# display.net
KiCad netlist of a schematic drawn in EAGLE
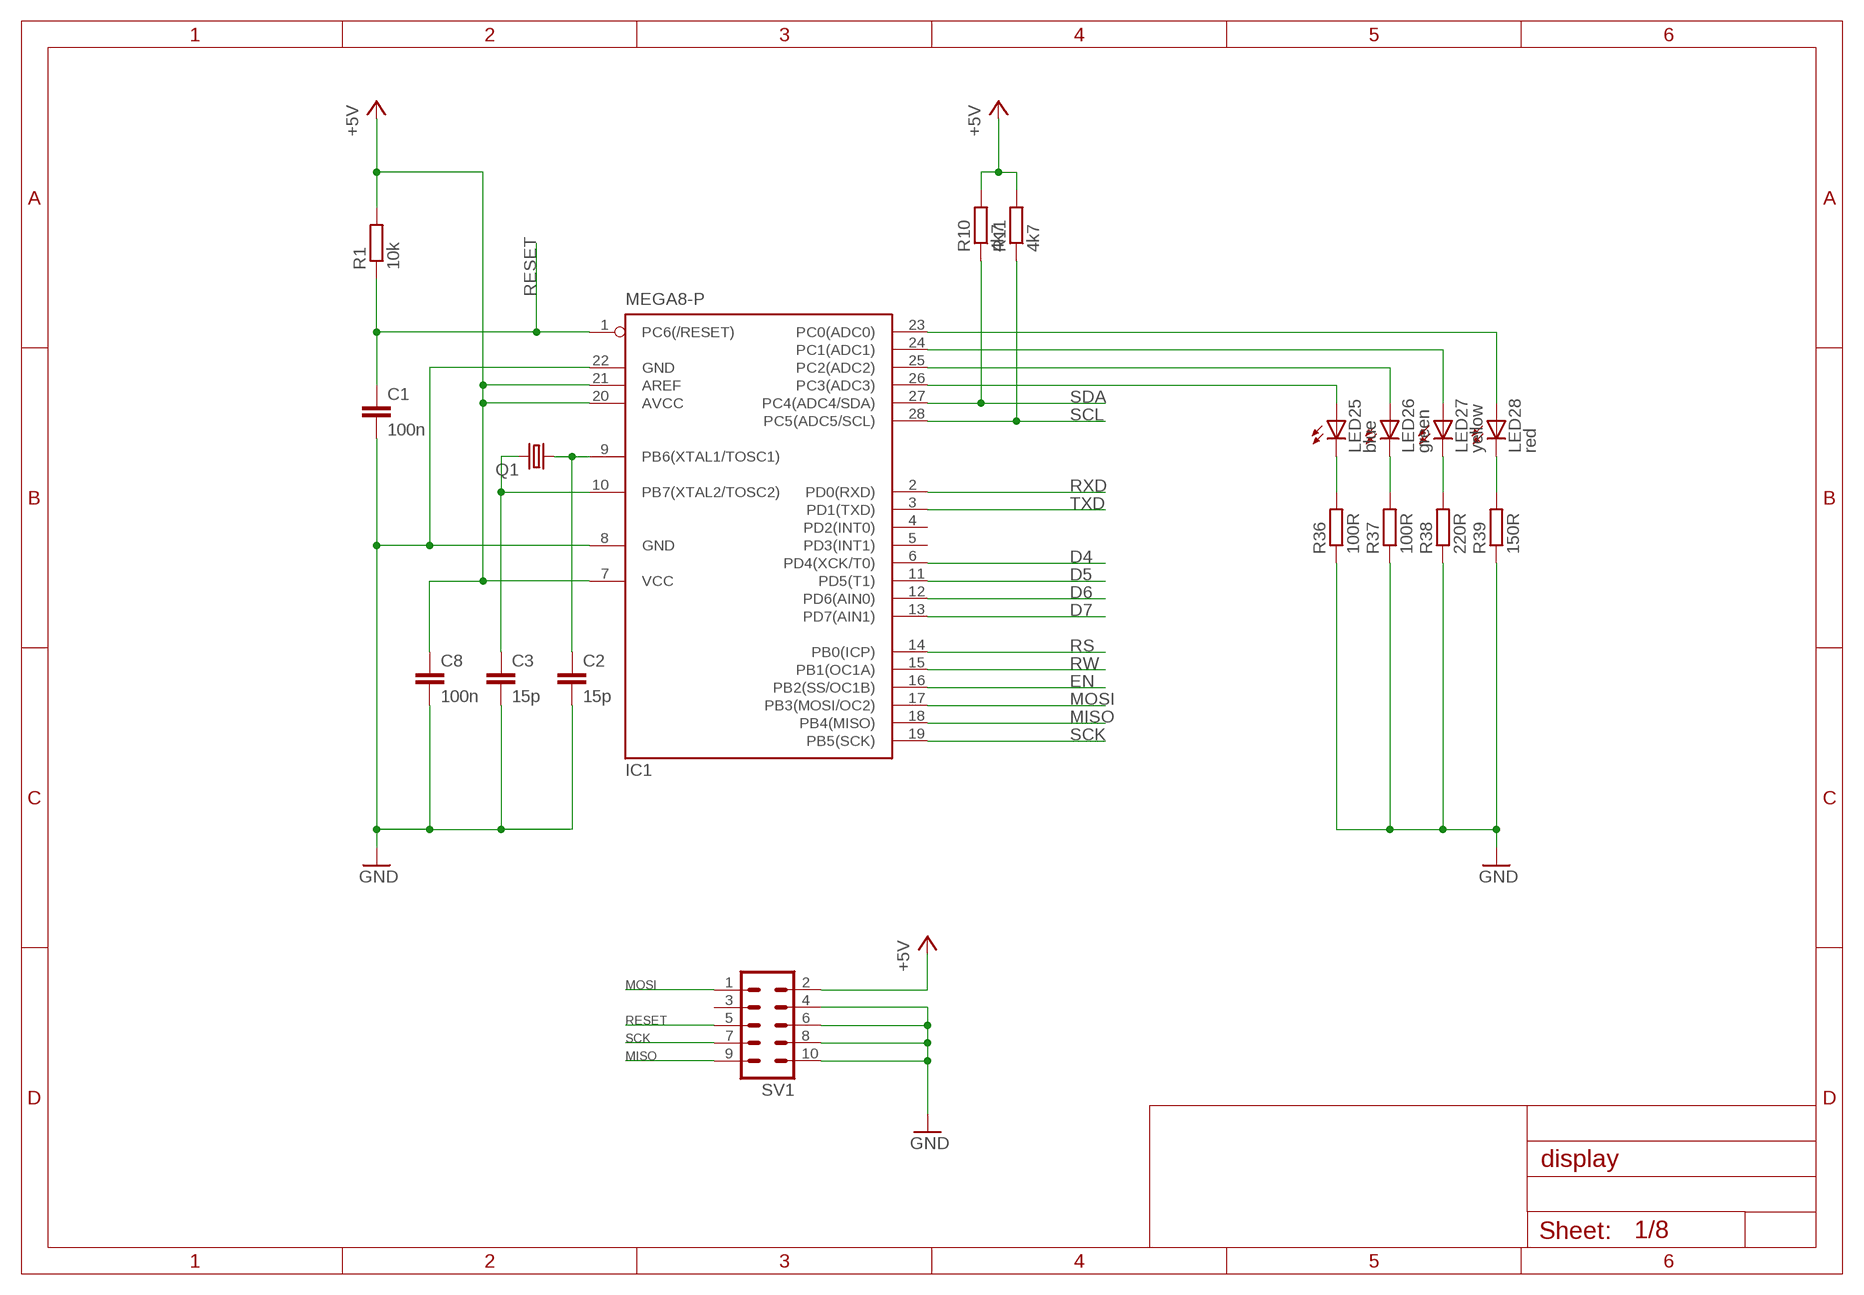
[diagram p0: schematic, sheet 1]
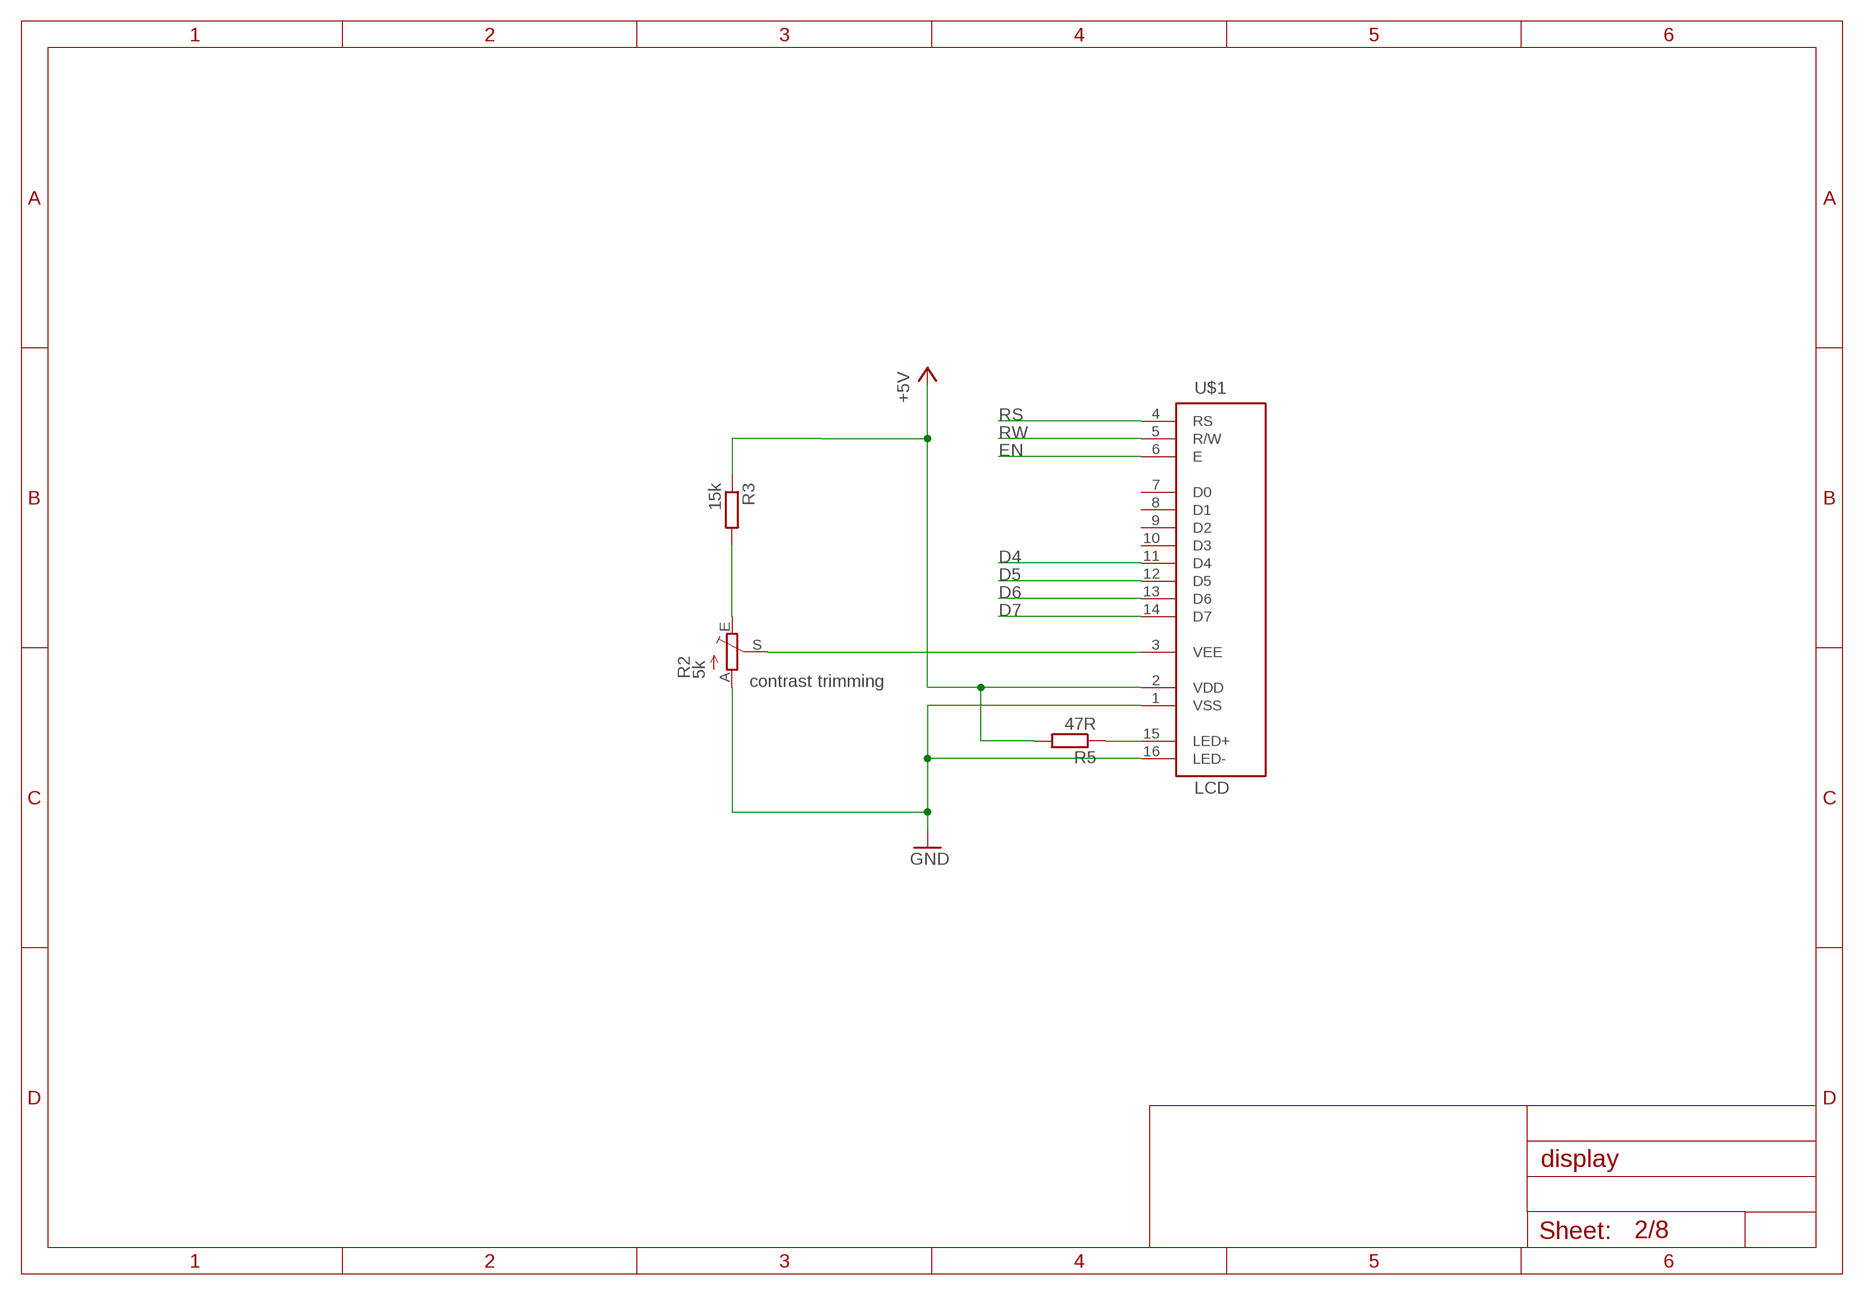
[diagram p1: schematic, sheet 2]
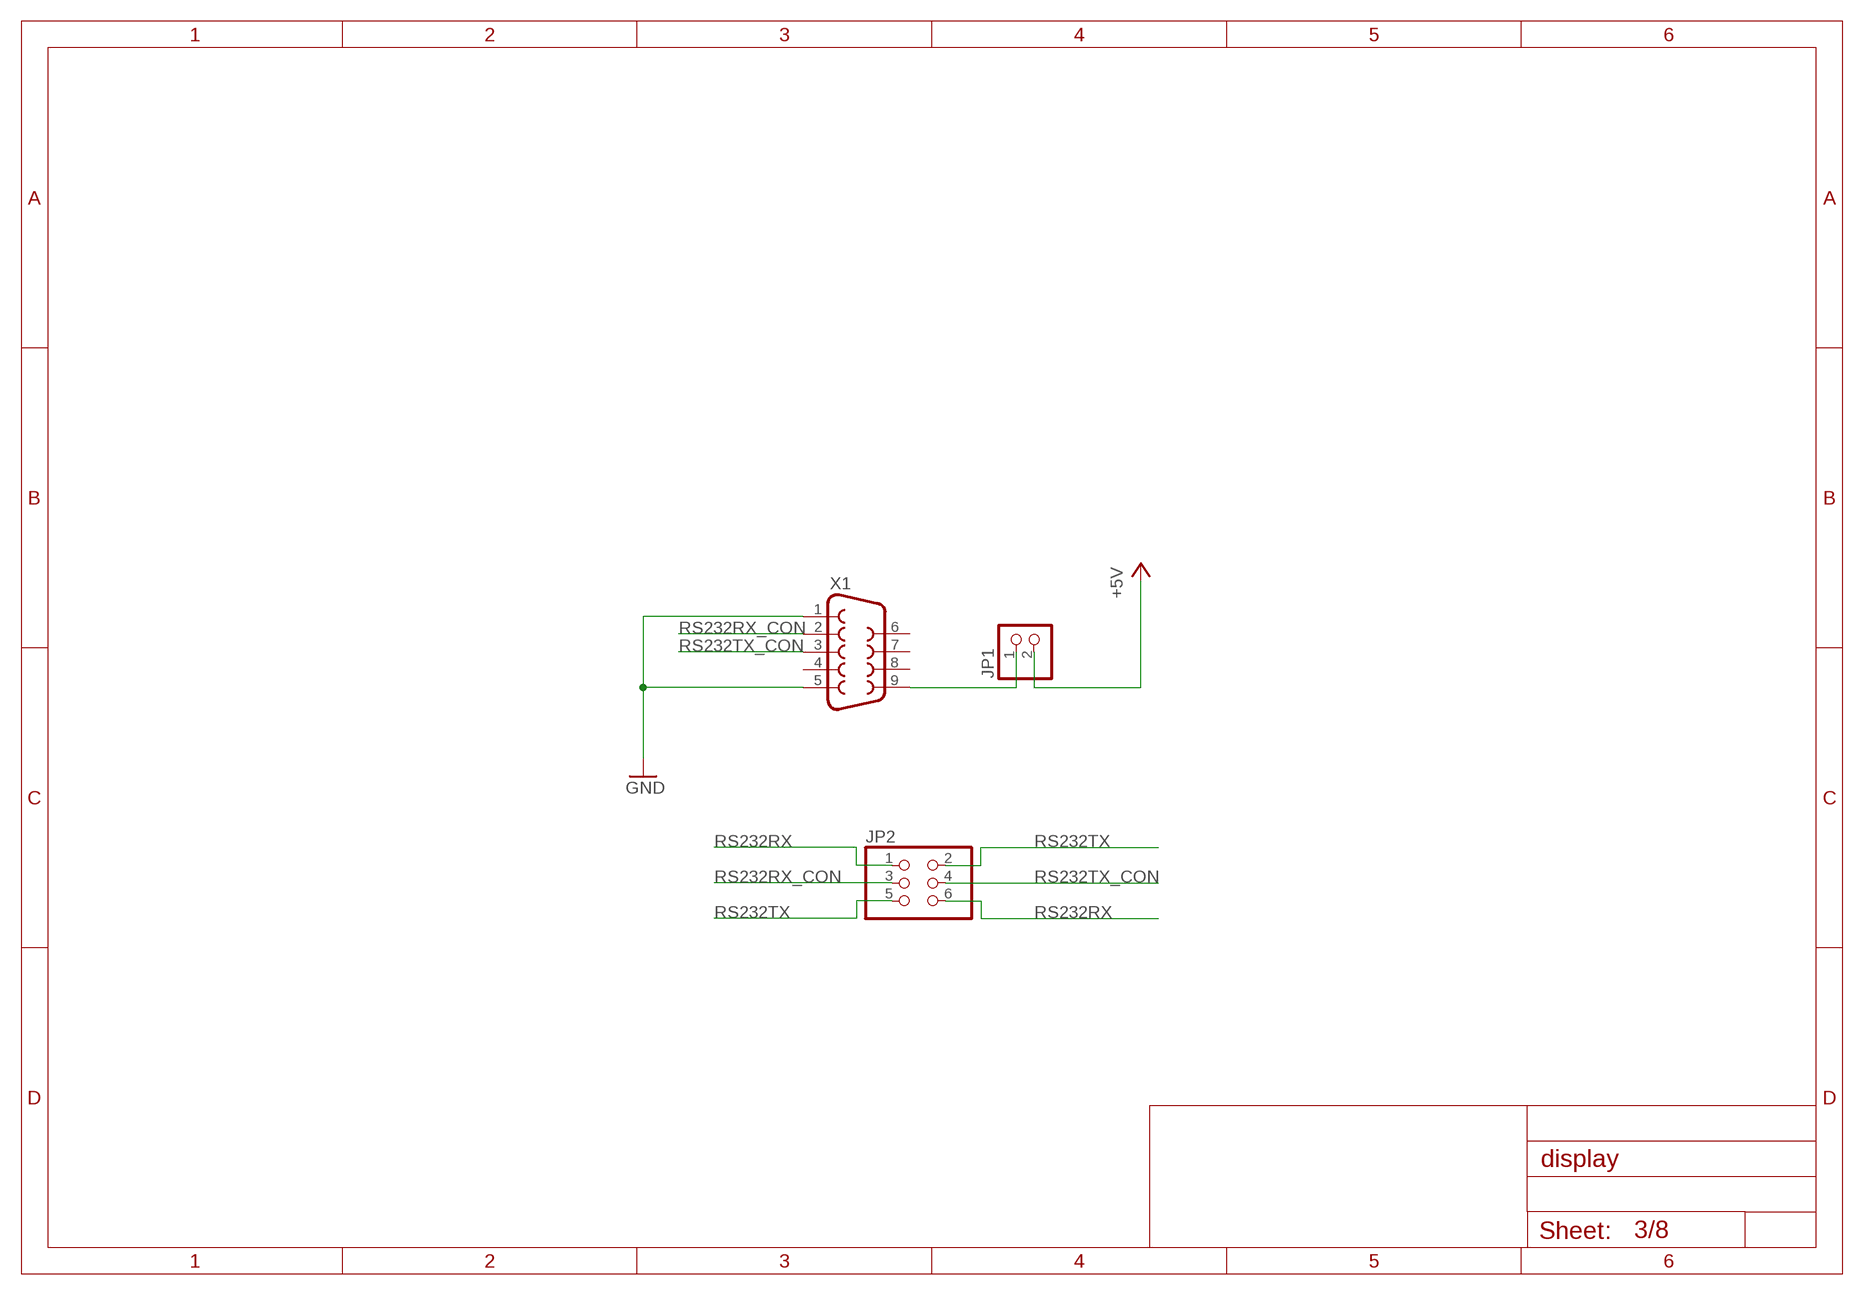
[diagram p2: schematic, sheet 3]
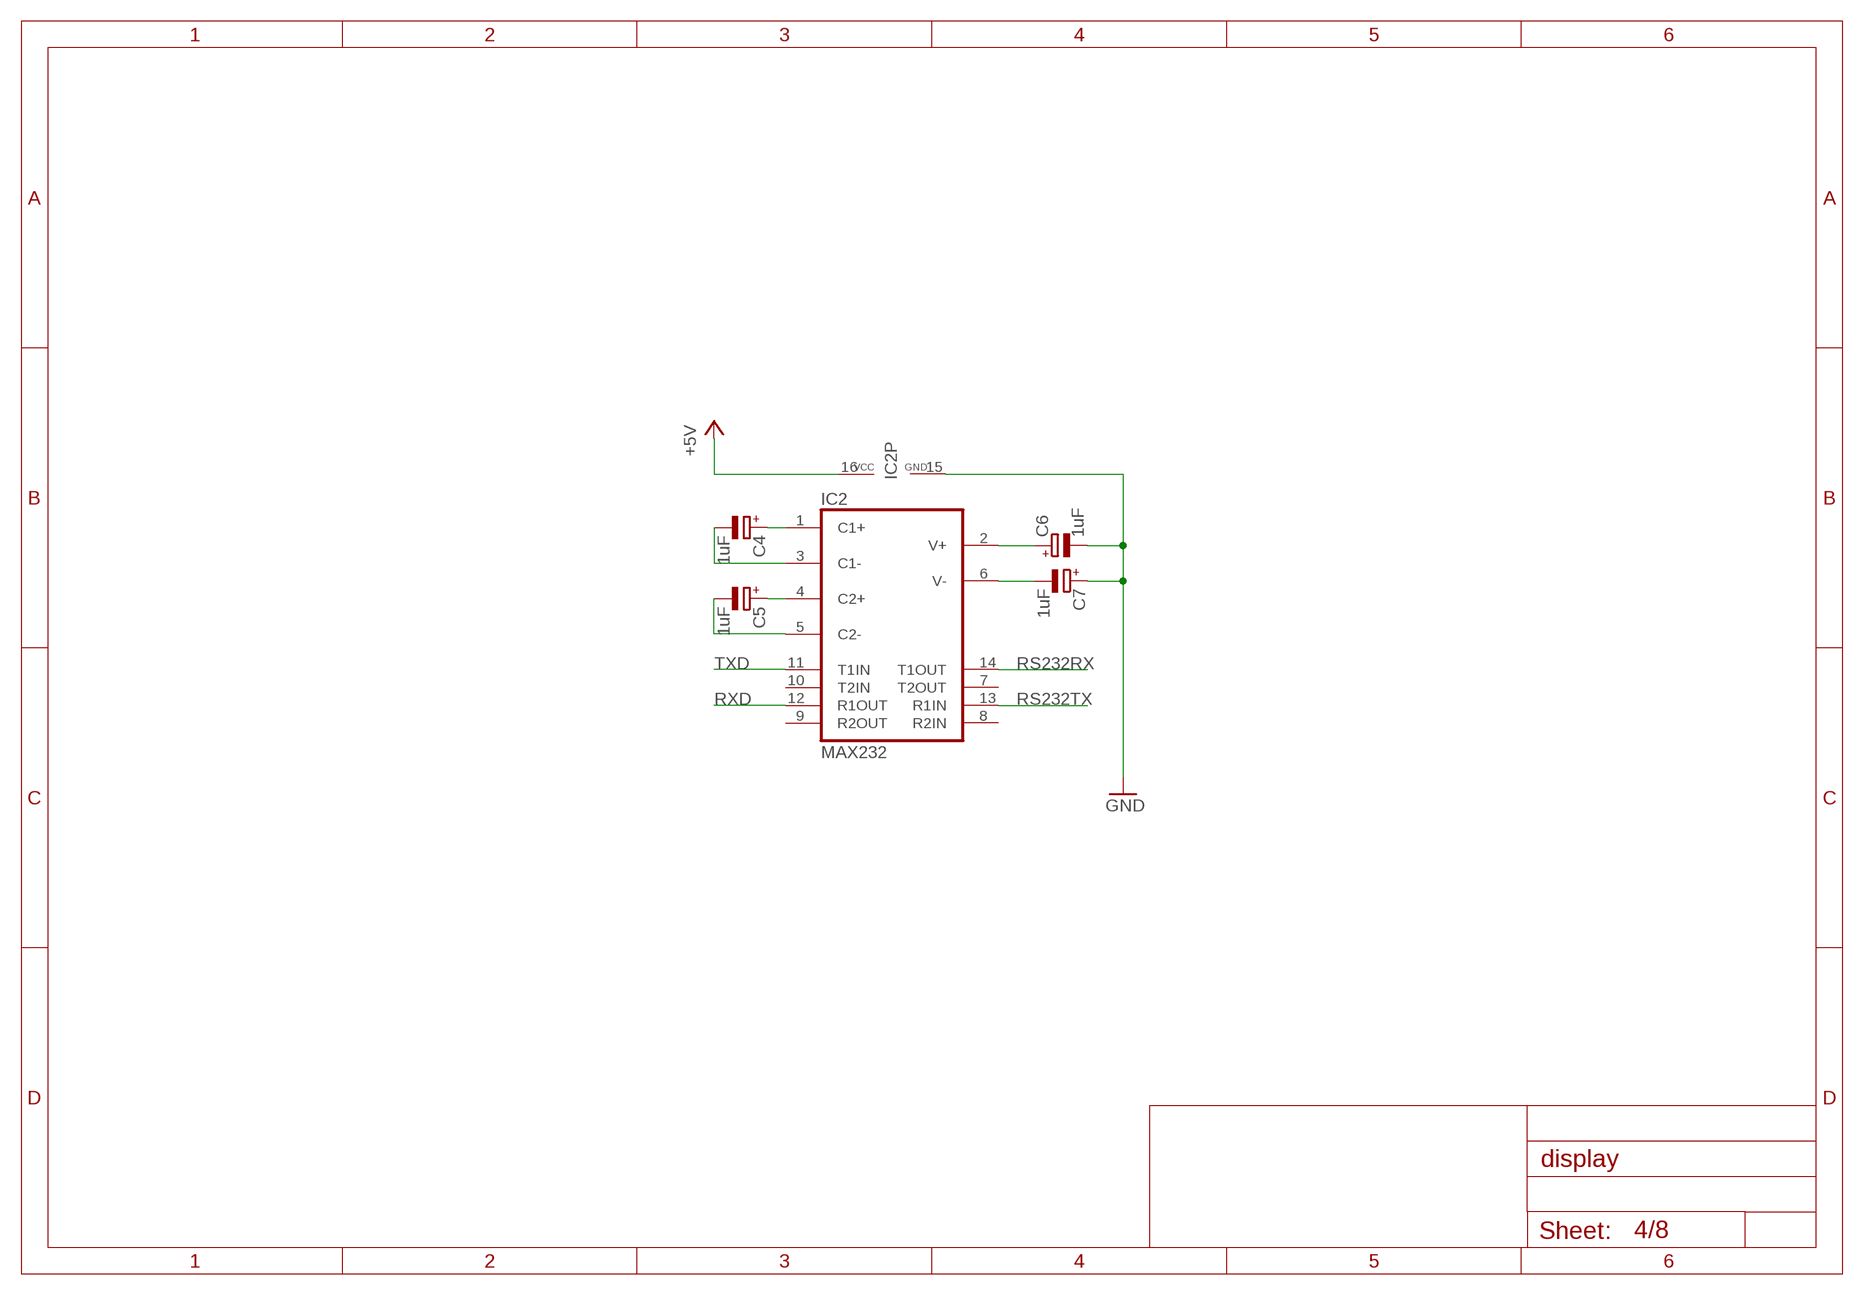
[diagram p3: schematic, sheet 4]
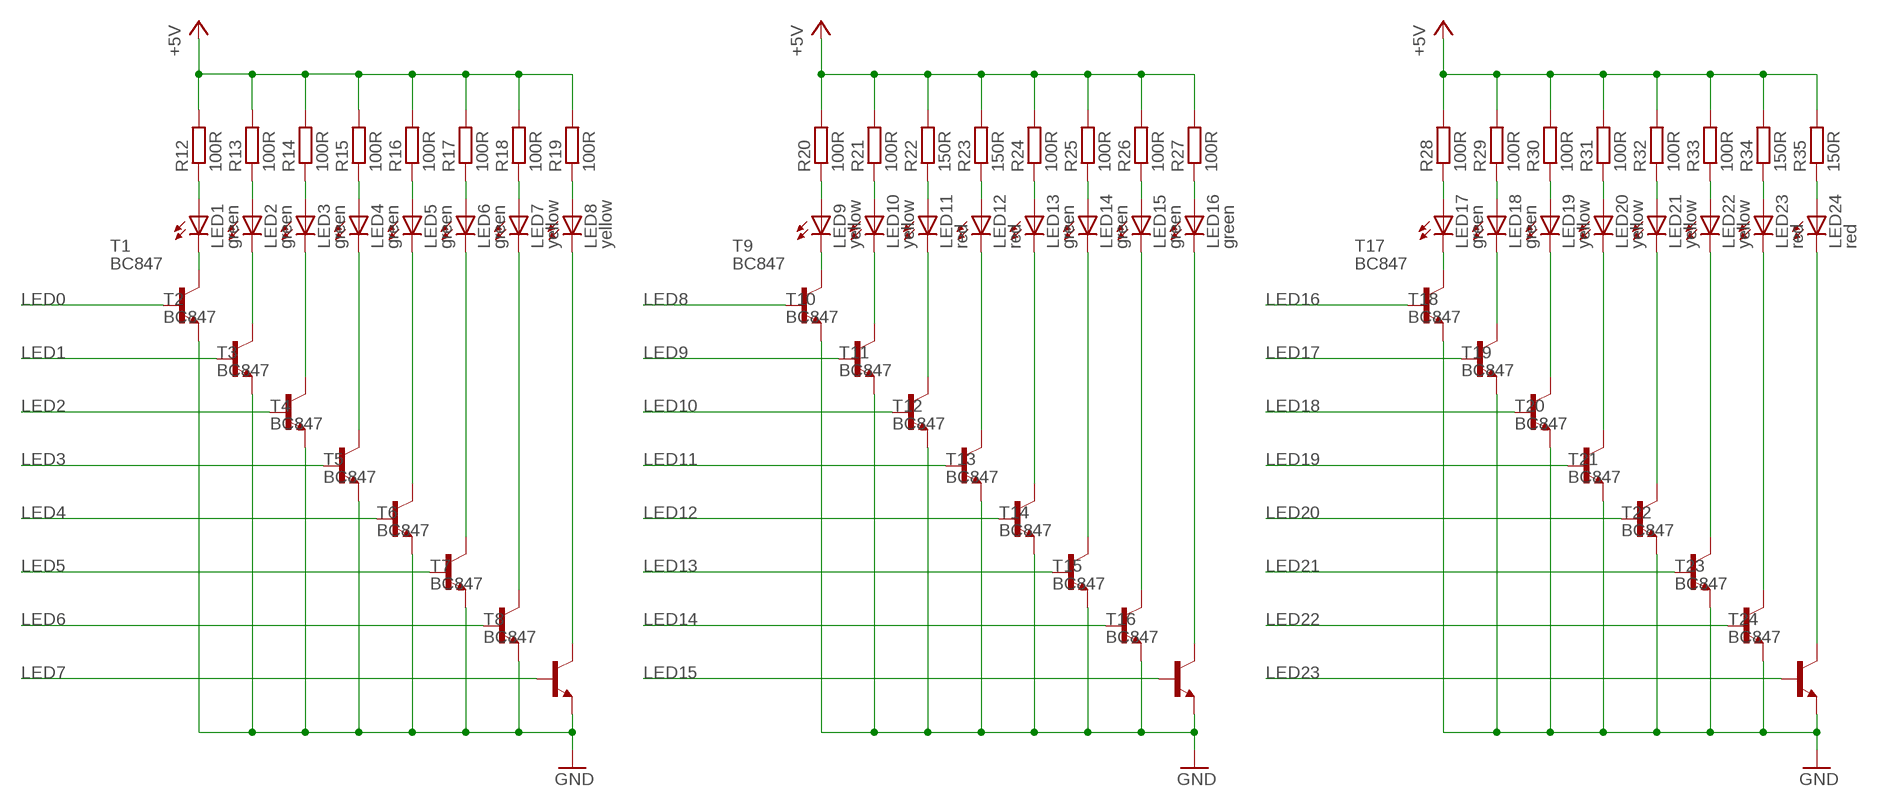
[diagram p4: schematic, sheet 5]
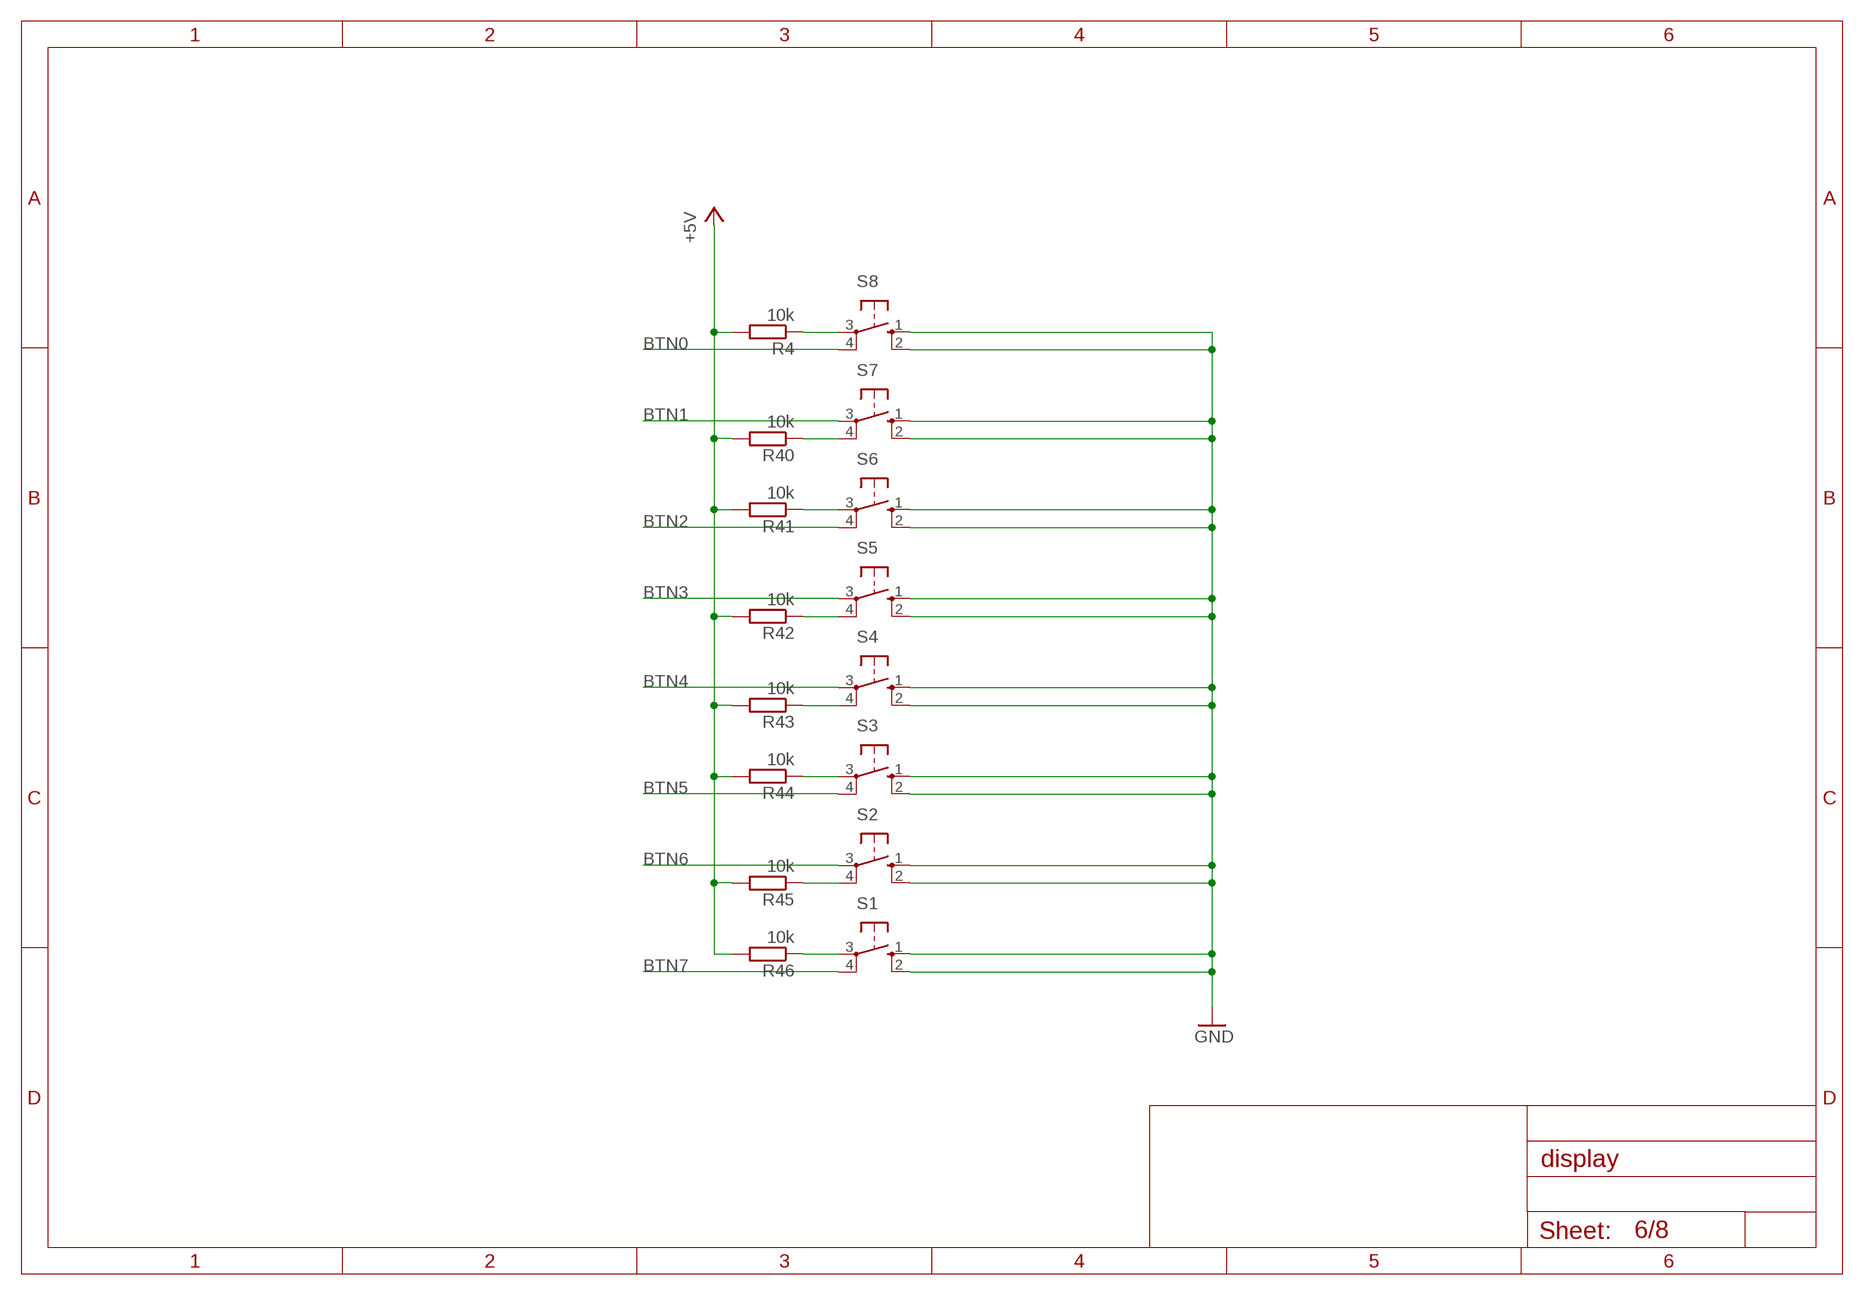
[diagram p5: schematic, sheet 6]
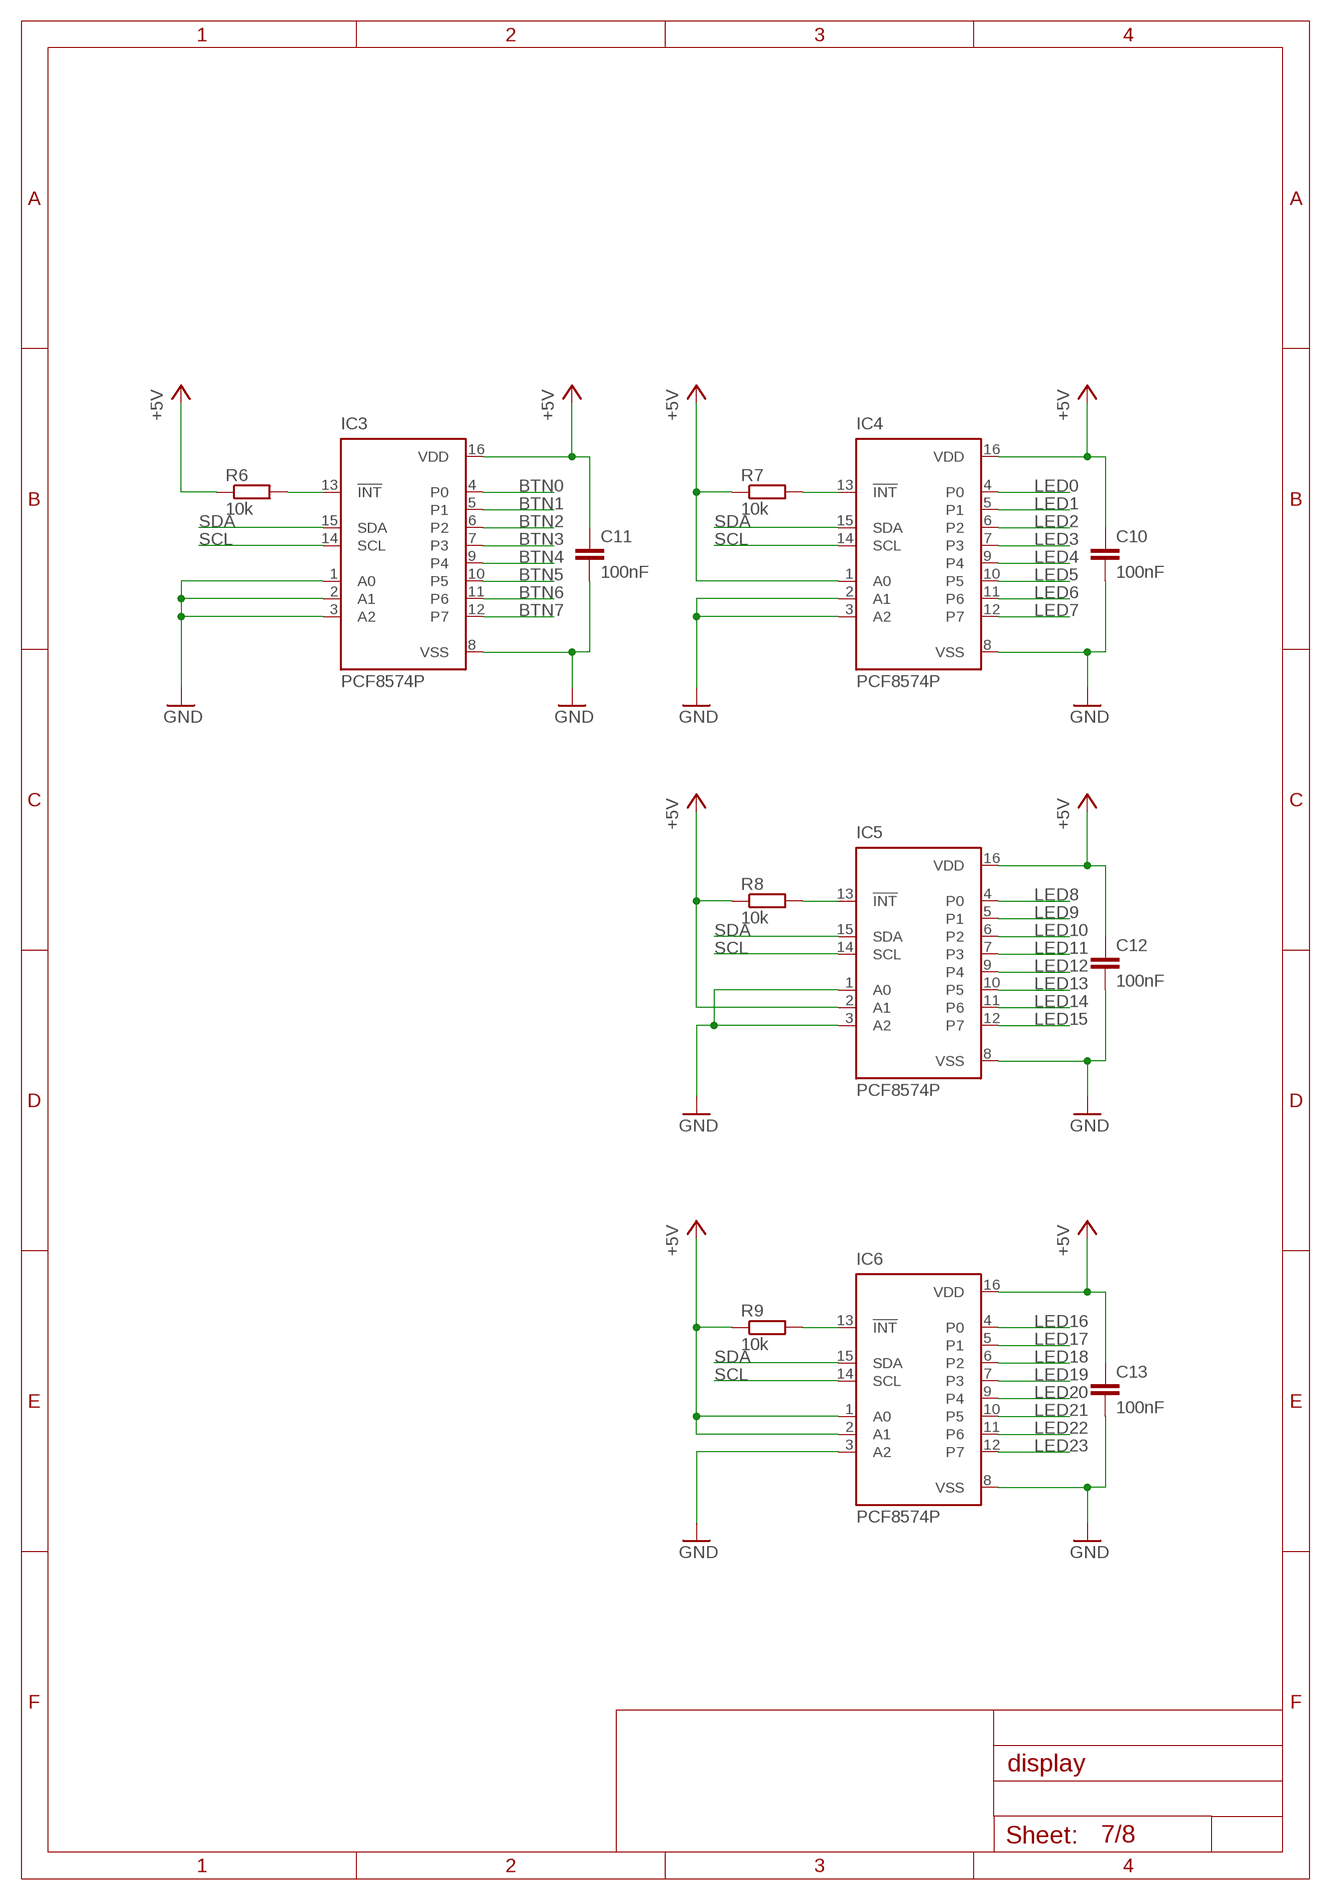
[diagram p6: schematic, sheet 7]
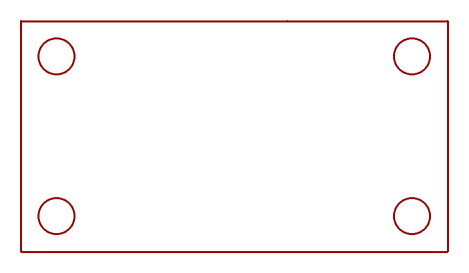
[diagram p7: schematic, sheet 8]

(export (version "E")
  (design (tool "Eeschema 10.0.6"))
  (components
    (comp (ref "R4")
      (value "10k")
      (footprint "eagle-import:R0805")
      (libsource (lib "eagle-import") (part "R-EU_R0805"))
    )
    (comp (ref "R40")
      (value "10k")
      (footprint "eagle-import:R0805")
      (libsource (lib "eagle-import") (part "R-EU_R0805"))
    )
    (comp (ref "R41")
      (value "10k")
      (footprint "eagle-import:R0805")
      (libsource (lib "eagle-import") (part "R-EU_R0805"))
    )
    (comp (ref "R42")
      (value "10k")
      (footprint "eagle-import:R0805")
      (libsource (lib "eagle-import") (part "R-EU_R0805"))
    )
    (comp (ref "R43")
      (value "10k")
      (footprint "eagle-import:R0805")
      (libsource (lib "eagle-import") (part "R-EU_R0805"))
    )
    (comp (ref "R44")
      (value "10k")
      (footprint "eagle-import:R0805")
      (libsource (lib "eagle-import") (part "R-EU_R0805"))
    )
    (comp (ref "R45")
      (value "10k")
      (footprint "eagle-import:R0805")
      (libsource (lib "eagle-import") (part "R-EU_R0805"))
    )
    (comp (ref "R46")
      (value "10k")
      (footprint "eagle-import:R0805")
      (libsource (lib "eagle-import") (part "R-EU_R0805"))
    )
    (comp (ref "S1")
      (value "10-XX")
      (footprint "eagle-import:B3F-10XX")
      (fields (field (name "MPN") "B3F-1000"))
      (libsource (lib "eagle-import") (part "10-XX"))
    )
    (comp (ref "S2")
      (value "10-XX")
      (footprint "eagle-import:B3F-10XX")
      (fields (field (name "MPN") "B3F-1000"))
      (libsource (lib "eagle-import") (part "10-XX"))
    )
    (comp (ref "S3")
      (value "10-XX")
      (footprint "eagle-import:B3F-10XX")
      (fields (field (name "MPN") "B3F-1000"))
      (libsource (lib "eagle-import") (part "10-XX"))
    )
    (comp (ref "S4")
      (value "10-XX")
      (footprint "eagle-import:B3F-10XX")
      (fields (field (name "MPN") "B3F-1000"))
      (libsource (lib "eagle-import") (part "10-XX"))
    )
    (comp (ref "S5")
      (value "10-XX")
      (footprint "eagle-import:B3F-10XX")
      (fields (field (name "MPN") "B3F-1000"))
      (libsource (lib "eagle-import") (part "10-XX"))
    )
    (comp (ref "S6")
      (value "10-XX")
      (footprint "eagle-import:B3F-10XX")
      (fields (field (name "MPN") "B3F-1000"))
      (libsource (lib "eagle-import") (part "10-XX"))
    )
    (comp (ref "S7")
      (value "10-XX")
      (footprint "eagle-import:B3F-10XX")
      (fields (field (name "MPN") "B3F-1000"))
      (libsource (lib "eagle-import") (part "10-XX"))
    )
    (comp (ref "S8")
      (value "10-XX")
      (footprint "eagle-import:B3F-10XX")
      (fields (field (name "MPN") "B3F-1000"))
      (libsource (lib "eagle-import") (part "10-XX"))
    )
    (comp (ref "R2")
      (value "5k")
      (footprint "eagle-import:PT-10")
      (libsource (lib "eagle-import") (part "TRIM_EU-PT10"))
    )
    (comp (ref "R3")
      (value "15k")
      (footprint "eagle-import:0207_10")
      (libsource (lib "eagle-import") (part "R-EU_0207/10"))
    )
    (comp (ref "R5")
      (value "47R")
      (footprint "eagle-import:0207_10")
      (libsource (lib "eagle-import") (part "R-EU_0207/10"))
    )
    (comp (ref "U$1")
      (value "LCD")
      (footprint "eagle-import:LCD")
      (libsource (lib "eagle-import") (part "LCD"))
    )
    (comp (ref "LED1")
      (value "green")
      (footprint "eagle-import:LED5MM")
      (libsource (lib "eagle-import") (part "LED5MM"))
    )
    (comp (ref "LED2")
      (value "green")
      (footprint "eagle-import:LED5MM")
      (libsource (lib "eagle-import") (part "LED5MM"))
    )
    (comp (ref "LED3")
      (value "green")
      (footprint "eagle-import:LED5MM")
      (libsource (lib "eagle-import") (part "LED5MM"))
    )
    (comp (ref "LED4")
      (value "green")
      (footprint "eagle-import:LED5MM")
      (libsource (lib "eagle-import") (part "LED5MM"))
    )
    (comp (ref "LED5")
      (value "green")
      (footprint "eagle-import:LED5MM")
      (libsource (lib "eagle-import") (part "LED5MM"))
    )
    (comp (ref "LED6")
      (value "green")
      (footprint "eagle-import:LED5MM")
      (libsource (lib "eagle-import") (part "LED5MM"))
    )
    (comp (ref "LED7")
      (value "yellow")
      (footprint "eagle-import:LED5MM")
      (libsource (lib "eagle-import") (part "LED5MM"))
    )
    (comp (ref "LED8")
      (value "yellow")
      (footprint "eagle-import:LED5MM")
      (libsource (lib "eagle-import") (part "LED5MM"))
    )
    (comp (ref "LED9")
      (value "yellow")
      (footprint "eagle-import:LED5MM")
      (libsource (lib "eagle-import") (part "LED5MM"))
    )
    (comp (ref "LED10")
      (value "yellow")
      (footprint "eagle-import:LED5MM")
      (libsource (lib "eagle-import") (part "LED5MM"))
    )
    (comp (ref "LED11")
      (value "red")
      (footprint "eagle-import:LED5MM")
      (libsource (lib "eagle-import") (part "LED5MM"))
    )
    (comp (ref "LED12")
      (value "red")
      (footprint "eagle-import:LED5MM")
      (libsource (lib "eagle-import") (part "LED5MM"))
    )
    (comp (ref "LED13")
      (value "green")
      (footprint "eagle-import:LED5MM")
      (libsource (lib "eagle-import") (part "LED5MM"))
    )
    (comp (ref "LED14")
      (value "green")
      (footprint "eagle-import:LED5MM")
      (libsource (lib "eagle-import") (part "LED5MM"))
    )
    (comp (ref "LED15")
      (value "green")
      (footprint "eagle-import:LED5MM")
      (libsource (lib "eagle-import") (part "LED5MM"))
    )
    (comp (ref "LED16")
      (value "green")
      (footprint "eagle-import:LED5MM")
      (libsource (lib "eagle-import") (part "LED5MM"))
    )
    (comp (ref "LED17")
      (value "green")
      (footprint "eagle-import:LED5MM")
      (fields (field (name "SPICEPREFIX") "L"))
      (libsource (lib "eagle-import") (part "LED5MM"))
    )
    (comp (ref "LED18")
      (value "green")
      (footprint "eagle-import:LED5MM")
      (fields (field (name "SPICEPREFIX") "X"))
      (libsource (lib "eagle-import") (part "LED5MM"))
    )
    (comp (ref "LED19")
      (value "yellow")
      (footprint "eagle-import:LED5MM")
      (fields (field (name "SPICEPREFIX") "B"))
      (libsource (lib "eagle-import") (part "LED5MM"))
    )
    (comp (ref "LED20")
      (value "yellow")
      (footprint "eagle-import:LED5MM")
      (fields (field (name "SPICEPREFIX") "L"))
      (libsource (lib "eagle-import") (part "LED5MM"))
    )
    (comp (ref "LED21")
      (value "yellow")
      (footprint "eagle-import:LED5MM")
      (fields (field (name "SPICEPREFIX") "L"))
      (libsource (lib "eagle-import") (part "LED5MM"))
    )
    (comp (ref "LED22")
      (value "yellow")
      (footprint "eagle-import:LED5MM")
      (fields (field (name "SPICEPREFIX") "L"))
      (libsource (lib "eagle-import") (part "LED5MM"))
    )
    (comp (ref "LED23")
      (value "red")
      (footprint "eagle-import:LED5MM")
      (fields (field (name "SPICEPREFIX") "L"))
      (libsource (lib "eagle-import") (part "LED5MM"))
    )
    (comp (ref "LED24")
      (value "red")
      (footprint "eagle-import:LED5MM")
      (fields (field (name "SPICEPREFIX") "L"))
      (libsource (lib "eagle-import") (part "LED5MM"))
    )
    (comp (ref "R12")
      (value "100R")
      (footprint "eagle-import:0207_10")
      (libsource (lib "eagle-import") (part "R-EU_0207/10"))
    )
    (comp (ref "R13")
      (value "100R")
      (footprint "eagle-import:0207_10")
      (libsource (lib "eagle-import") (part "R-EU_0207/10"))
    )
    (comp (ref "R14")
      (value "100R")
      (footprint "eagle-import:0207_10")
      (libsource (lib "eagle-import") (part "R-EU_0207/10"))
    )
    (comp (ref "R15")
      (value "100R")
      (footprint "eagle-import:0207_10")
      (libsource (lib "eagle-import") (part "R-EU_0207/10"))
    )
    (comp (ref "R16")
      (value "100R")
      (footprint "eagle-import:0207_10")
      (libsource (lib "eagle-import") (part "R-EU_0207/10"))
    )
    (comp (ref "R17")
      (value "100R")
      (footprint "eagle-import:0207_10")
      (libsource (lib "eagle-import") (part "R-EU_0207/10"))
    )
    (comp (ref "R18")
      (value "100R")
      (footprint "eagle-import:0207_10")
      (libsource (lib "eagle-import") (part "R-EU_0207/10"))
    )
    (comp (ref "R19")
      (value "100R")
      (footprint "eagle-import:0207_10")
      (libsource (lib "eagle-import") (part "R-EU_0207/10"))
    )
    (comp (ref "R20")
      (value "100R")
      (footprint "eagle-import:0207_10")
      (libsource (lib "eagle-import") (part "R-EU_0207/10"))
    )
    (comp (ref "R21")
      (value "100R")
      (footprint "eagle-import:0207_10")
      (libsource (lib "eagle-import") (part "R-EU_0207/10"))
    )
    (comp (ref "R22")
      (value "150R")
      (footprint "eagle-import:0207_10")
      (libsource (lib "eagle-import") (part "R-EU_0207/10"))
    )
    (comp (ref "R23")
      (value "150R")
      (footprint "eagle-import:0207_10")
      (libsource (lib "eagle-import") (part "R-EU_0207/10"))
    )
    (comp (ref "R24")
      (value "100R")
      (footprint "eagle-import:0207_10")
      (libsource (lib "eagle-import") (part "R-EU_0207/10"))
    )
    (comp (ref "R25")
      (value "100R")
      (footprint "eagle-import:0207_10")
      (libsource (lib "eagle-import") (part "R-EU_0207/10"))
    )
    (comp (ref "R26")
      (value "100R")
      (footprint "eagle-import:0207_10")
      (libsource (lib "eagle-import") (part "R-EU_0207/10"))
    )
    (comp (ref "R27")
      (value "100R")
      (footprint "eagle-import:0207_10")
      (libsource (lib "eagle-import") (part "R-EU_0207/10"))
    )
    (comp (ref "R28")
      (value "100R")
      (footprint "eagle-import:0207_10")
      (libsource (lib "eagle-import") (part "R-EU_0207/10"))
    )
    (comp (ref "R29")
      (value "100R")
      (footprint "eagle-import:0207_10")
      (libsource (lib "eagle-import") (part "R-EU_0207/10"))
    )
    (comp (ref "R30")
      (value "100R")
      (footprint "eagle-import:0207_10")
      (libsource (lib "eagle-import") (part "R-EU_0207/10"))
    )
    (comp (ref "R31")
      (value "100R")
      (footprint "eagle-import:0207_10")
      (libsource (lib "eagle-import") (part "R-EU_0207/10"))
    )
    (comp (ref "R32")
      (value "100R")
      (footprint "eagle-import:0207_10")
      (libsource (lib "eagle-import") (part "R-EU_0207/10"))
    )
    (comp (ref "R33")
      (value "100R")
      (footprint "eagle-import:0207_10")
      (libsource (lib "eagle-import") (part "R-EU_0207/10"))
    )
    (comp (ref "R34")
      (value "150R")
      (footprint "eagle-import:0207_10")
      (libsource (lib "eagle-import") (part "R-EU_0207/10"))
    )
    (comp (ref "R35")
      (value "150R")
      (footprint "eagle-import:0207_10")
      (libsource (lib "eagle-import") (part "R-EU_0207/10"))
    )
    (comp (ref "T1")
      (value "BC847")
      (footprint "eagle-import:SOT23")
      (libsource (lib "eagle-import") (part "BC847"))
    )
    (comp (ref "T2")
      (value "BC847")
      (footprint "eagle-import:SOT23")
      (libsource (lib "eagle-import") (part "BC847"))
    )
    (comp (ref "T3")
      (value "BC847")
      (footprint "eagle-import:SOT23")
      (libsource (lib "eagle-import") (part "BC847"))
    )
    (comp (ref "T4")
      (value "BC847")
      (footprint "eagle-import:SOT23")
      (libsource (lib "eagle-import") (part "BC847"))
    )
    (comp (ref "T5")
      (value "BC847")
      (footprint "eagle-import:SOT23")
      (libsource (lib "eagle-import") (part "BC847"))
    )
    (comp (ref "T6")
      (value "BC847")
      (footprint "eagle-import:SOT23")
      (libsource (lib "eagle-import") (part "BC847"))
    )
    (comp (ref "T7")
      (value "BC847")
      (footprint "eagle-import:SOT23")
      (libsource (lib "eagle-import") (part "BC847"))
    )
    (comp (ref "T8")
      (value "BC847")
      (footprint "eagle-import:SOT23")
      (libsource (lib "eagle-import") (part "BC847"))
    )
    (comp (ref "T9")
      (value "BC847")
      (footprint "eagle-import:SOT23")
      (libsource (lib "eagle-import") (part "BC847"))
    )
    (comp (ref "T10")
      (value "BC847")
      (footprint "eagle-import:SOT23")
      (libsource (lib "eagle-import") (part "BC847"))
    )
    (comp (ref "T11")
      (value "BC847")
      (footprint "eagle-import:SOT23")
      (libsource (lib "eagle-import") (part "BC847"))
    )
    (comp (ref "T12")
      (value "BC847")
      (footprint "eagle-import:SOT23")
      (libsource (lib "eagle-import") (part "BC847"))
    )
    (comp (ref "T13")
      (value "BC847")
      (footprint "eagle-import:SOT23")
      (libsource (lib "eagle-import") (part "BC847"))
    )
    (comp (ref "T14")
      (value "BC847")
      (footprint "eagle-import:SOT23")
      (libsource (lib "eagle-import") (part "BC847"))
    )
    (comp (ref "T15")
      (value "BC847")
      (footprint "eagle-import:SOT23")
      (libsource (lib "eagle-import") (part "BC847"))
    )
    (comp (ref "T16")
      (value "BC847")
      (footprint "eagle-import:SOT23")
      (fields (field (name "SPICEPREFIX") "J"))
      (libsource (lib "eagle-import") (part "BC847"))
    )
    (comp (ref "T17")
      (value "BC847")
      (footprint "eagle-import:SOT23")
      (libsource (lib "eagle-import") (part "BC847"))
    )
    (comp (ref "T18")
      (value "BC847")
      (footprint "eagle-import:SOT23")
      (libsource (lib "eagle-import") (part "BC847"))
    )
    (comp (ref "T19")
      (value "BC847")
      (footprint "eagle-import:SOT23")
      (libsource (lib "eagle-import") (part "BC847"))
    )
    (comp (ref "T20")
      (value "BC847")
      (footprint "eagle-import:SOT23")
      (libsource (lib "eagle-import") (part "BC847"))
    )
    (comp (ref "T21")
      (value "BC847")
      (footprint "eagle-import:SOT23")
      (libsource (lib "eagle-import") (part "BC847"))
    )
    (comp (ref "T22")
      (value "BC847")
      (footprint "eagle-import:SOT23")
      (libsource (lib "eagle-import") (part "BC847"))
    )
    (comp (ref "T23")
      (value "BC847")
      (footprint "eagle-import:SOT23")
      (libsource (lib "eagle-import") (part "BC847"))
    )
    (comp (ref "T24")
      (value "BC847")
      (footprint "eagle-import:SOT23")
      (libsource (lib "eagle-import") (part "BC847"))
    )
    (comp (ref "JP1")
      (value "PINHD-1X2")
      (footprint "eagle-import:1X02")
      (libsource (lib "eagle-import") (part "PINHD-1X2"))
    )
    (comp (ref "JP2")
      (value "PINHD-2X3")
      (footprint "eagle-import:2X03")
      (libsource (lib "eagle-import") (part "PINHD-2X3"))
    )
    (comp (ref "X1")
      (value "F09HP")
      (footprint "eagle-import:F09HP")
      (libsource (lib "eagle-import") (part "F09HP"))
    )
    (comp (ref "C1")
      (value "100n")
      (footprint "eagle-import:C025-025X050")
      (libsource (lib "eagle-import") (part "C-EU025-025X050"))
    )
    (comp (ref "C2")
      (value "15p")
      (footprint "eagle-import:C025-025X050")
      (libsource (lib "eagle-import") (part "C-EU025-025X050"))
    )
    (comp (ref "C3")
      (value "15p")
      (footprint "eagle-import:C025-025X050")
      (libsource (lib "eagle-import") (part "C-EU025-025X050"))
    )
    (comp (ref "C8")
      (value "100n")
      (footprint "eagle-import:C025-025X050")
      (libsource (lib "eagle-import") (part "C-EU025-025X050"))
    )
    (comp (ref "IC1")
      (value "MEGA8-P")
      (footprint "eagle-import:DIL28-3")
      (libsource (lib "eagle-import") (part "MEGA8-P"))
    )
    (comp (ref "LED25")
      (value "blue")
      (footprint "eagle-import:LED3MM")
      (libsource (lib "eagle-import") (part "LED3MM"))
    )
    (comp (ref "LED26")
      (value "green")
      (footprint "eagle-import:LED3MM")
      (libsource (lib "eagle-import") (part "LED3MM"))
    )
    (comp (ref "LED27")
      (value "yellow")
      (footprint "eagle-import:LED3MM")
      (libsource (lib "eagle-import") (part "LED3MM"))
    )
    (comp (ref "LED28")
      (value "red")
      (footprint "eagle-import:LED3MM")
      (libsource (lib "eagle-import") (part "LED3MM"))
    )
    (comp (ref "Q1")
      (value "CRYSTALHC49U-V")
      (footprint "eagle-import:HC49U-V")
      (libsource (lib "eagle-import") (part "CRYSTALHC49U-V"))
    )
    (comp (ref "R1")
      (value "10k")
      (footprint "eagle-import:0207_10")
      (libsource (lib "eagle-import") (part "R-EU_0207/10"))
    )
    (comp (ref "R10")
      (value "4k7")
      (footprint "eagle-import:0207_10")
      (libsource (lib "eagle-import") (part "R-EU_0207/10"))
    )
    (comp (ref "R11")
      (value "4k7")
      (footprint "eagle-import:0207_10")
      (libsource (lib "eagle-import") (part "R-EU_0207/10"))
    )
    (comp (ref "R36")
      (value "100R")
      (footprint "eagle-import:0207_10")
      (libsource (lib "eagle-import") (part "R-EU_0207/10"))
    )
    (comp (ref "R37")
      (value "100R")
      (footprint "eagle-import:0207_10")
      (libsource (lib "eagle-import") (part "R-EU_0207/10"))
    )
    (comp (ref "R38")
      (value "220R")
      (footprint "eagle-import:0207_10")
      (libsource (lib "eagle-import") (part "R-EU_0207/10"))
    )
    (comp (ref "R39")
      (value "150R")
      (footprint "eagle-import:0207_10")
      (libsource (lib "eagle-import") (part "R-EU_0207/10"))
    )
    (comp (ref "SV1")
      (value "ML10")
      (footprint "eagle-import:ML10")
      (libsource (lib "eagle-import") (part "ML10"))
    )
    (comp (ref "C10")
      (value "100nF")
      (footprint "eagle-import:C025-025X050")
      (libsource (lib "eagle-import") (part "C-EU025-025X050"))
    )
    (comp (ref "C11")
      (value "100nF")
      (footprint "eagle-import:C025-025X050")
      (libsource (lib "eagle-import") (part "C-EU025-025X050"))
    )
    (comp (ref "C12")
      (value "100nF")
      (footprint "eagle-import:C025-025X050")
      (libsource (lib "eagle-import") (part "C-EU025-025X050"))
    )
    (comp (ref "C13")
      (value "100nF")
      (footprint "eagle-import:C025-025X050")
      (libsource (lib "eagle-import") (part "C-EU025-025X050"))
    )
    (comp (ref "IC3")
      (value "PCF8574P")
      (footprint "eagle-import:DIL16")
      (fields (field (name "MPN") "PCF8574PN"))
      (libsource (lib "eagle-import") (part "PCF8574P"))
    )
    (comp (ref "IC4")
      (value "PCF8574P")
      (footprint "eagle-import:DIL16")
      (fields (field (name "MPN") "PCF8574PN"))
      (libsource (lib "eagle-import") (part "PCF8574P"))
    )
    (comp (ref "IC5")
      (value "PCF8574P")
      (footprint "eagle-import:DIL16")
      (fields (field (name "MPN") "PCF8574PN"))
      (libsource (lib "eagle-import") (part "PCF8574P"))
    )
    (comp (ref "IC6")
      (value "PCF8574P")
      (footprint "eagle-import:DIL16")
      (fields (field (name "MPN") "PCF8574PN"))
      (libsource (lib "eagle-import") (part "PCF8574P"))
    )
    (comp (ref "R6")
      (value "10k")
      (footprint "eagle-import:0207_10")
      (libsource (lib "eagle-import") (part "R-EU_0207/10"))
    )
    (comp (ref "R7")
      (value "10k")
      (footprint "eagle-import:0207_10")
      (libsource (lib "eagle-import") (part "R-EU_0207/10"))
    )
    (comp (ref "R8")
      (value "10k")
      (footprint "eagle-import:0207_10")
      (libsource (lib "eagle-import") (part "R-EU_0207/10"))
    )
    (comp (ref "R9")
      (value "10k")
      (footprint "eagle-import:0207_10")
      (libsource (lib "eagle-import") (part "R-EU_0207/10"))
    )
    (comp (ref "C4")
      (value "1uF")
      (footprint "eagle-import:E2,5-5")
      (libsource (lib "eagle-import") (part "CPOL-EUE2.5-5"))
    )
    (comp (ref "C5")
      (value "1uF")
      (footprint "eagle-import:E2,5-5")
      (libsource (lib "eagle-import") (part "CPOL-EUE2.5-5"))
    )
    (comp (ref "C6")
      (value "1uF")
      (footprint "eagle-import:E2,5-5")
      (libsource (lib "eagle-import") (part "CPOL-EUE2.5-5"))
    )
    (comp (ref "C7")
      (value "1uF")
      (footprint "eagle-import:E2,5-5")
      (libsource (lib "eagle-import") (part "CPOL-EUE2.5-5"))
    )
    (comp (ref "IC2")
      (value "MAX232")
      (footprint "eagle-import:DIL16")
      (fields (field (name "MF") "MAXIM") (field (name "MPN") "MAX232ACPE+"))
      (libsource (lib "eagle-import") (part "MAX232"))
    )
    (comp (ref "U$2")
      (value "DISPLAY_FRAME")
      (footprint "eagle-import:DISPLAY_FRAME")
      (libsource (lib "eagle-import") (part "DISPLAY_FRAME"))
    )
  )
  (nets
    (net (code "1") (name "+5V") (class "Default")
      (node (ref "C10") (pin "1") (pinfunction "1_1") (pintype "passive"))
      (node (ref "C11") (pin "1") (pinfunction "1_1") (pintype "passive"))
      (node (ref "C12") (pin "1") (pinfunction "1_1") (pintype "passive"))
      (node (ref "C13") (pin "1") (pinfunction "1_1") (pintype "passive"))
      (node (ref "C8") (pin "1") (pinfunction "1_1") (pintype "passive"))
      (node (ref "IC1") (pin "20") (pinfunction "AVCC_20") (pintype "power_in"))
      (node (ref "IC1") (pin "21") (pinfunction "AREF_21") (pintype "passive"))
      (node (ref "IC1") (pin "7") (pinfunction "VCC_7") (pintype "power_in"))
      (node (ref "IC2") (pin "16") (pinfunction "VCC_16") (pintype "power_in"))
      (node (ref "IC3") (pin "16") (pinfunction "VDD_16") (pintype "power_in"))
      (node (ref "IC4") (pin "1") (pinfunction "A0_1") (pintype "input"))
      (node (ref "IC4") (pin "16") (pinfunction "VDD_16") (pintype "power_in"))
      (node (ref "IC5") (pin "16") (pinfunction "VDD_16") (pintype "power_in"))
      (node (ref "IC5") (pin "2") (pinfunction "A1_2") (pintype "input"))
      (node (ref "IC6") (pin "1") (pinfunction "A0_1") (pintype "input"))
      (node (ref "IC6") (pin "16") (pinfunction "VDD_16") (pintype "power_in"))
      (node (ref "IC6") (pin "2") (pinfunction "A1_2") (pintype "input"))
      (node (ref "JP1") (pin "2") (pinfunction "2_2") (pintype "passive"))
      (node (ref "R1") (pin "2") (pinfunction "2_2") (pintype "passive"))
      (node (ref "R10") (pin "2") (pinfunction "2_2") (pintype "passive"))
      (node (ref "R11") (pin "2") (pinfunction "2_2") (pintype "passive"))
      (node (ref "R12") (pin "2") (pinfunction "2_2") (pintype "passive"))
      (node (ref "R13") (pin "2") (pinfunction "2_2") (pintype "passive"))
      (node (ref "R14") (pin "2") (pinfunction "2_2") (pintype "passive"))
      (node (ref "R15") (pin "2") (pinfunction "2_2") (pintype "passive"))
      (node (ref "R16") (pin "2") (pinfunction "2_2") (pintype "passive"))
      (node (ref "R17") (pin "2") (pinfunction "2_2") (pintype "passive"))
      (node (ref "R18") (pin "2") (pinfunction "2_2") (pintype "passive"))
      (node (ref "R19") (pin "2") (pinfunction "2_2") (pintype "passive"))
      (node (ref "R20") (pin "2") (pinfunction "2_2") (pintype "passive"))
      (node (ref "R21") (pin "2") (pinfunction "2_2") (pintype "passive"))
      (node (ref "R22") (pin "2") (pinfunction "2_2") (pintype "passive"))
      (node (ref "R23") (pin "2") (pinfunction "2_2") (pintype "passive"))
      (node (ref "R24") (pin "2") (pinfunction "2_2") (pintype "passive"))
      (node (ref "R25") (pin "2") (pinfunction "2_2") (pintype "passive"))
      (node (ref "R26") (pin "2") (pinfunction "2_2") (pintype "passive"))
      (node (ref "R27") (pin "2") (pinfunction "2_2") (pintype "passive"))
      (node (ref "R28") (pin "2") (pinfunction "2_2") (pintype "passive"))
      (node (ref "R29") (pin "2") (pinfunction "2_2") (pintype "passive"))
      (node (ref "R3") (pin "1") (pinfunction "1_1") (pintype "passive"))
      (node (ref "R30") (pin "2") (pinfunction "2_2") (pintype "passive"))
      (node (ref "R31") (pin "2") (pinfunction "2_2") (pintype "passive"))
      (node (ref "R32") (pin "2") (pinfunction "2_2") (pintype "passive"))
      (node (ref "R33") (pin "2") (pinfunction "2_2") (pintype "passive"))
      (node (ref "R34") (pin "2") (pinfunction "2_2") (pintype "passive"))
      (node (ref "R35") (pin "2") (pinfunction "2_2") (pintype "passive"))
      (node (ref "R4") (pin "2") (pinfunction "2_2") (pintype "passive"))
      (node (ref "R40") (pin "2") (pinfunction "2_2") (pintype "passive"))
      (node (ref "R41") (pin "2") (pinfunction "2_2") (pintype "passive"))
      (node (ref "R42") (pin "2") (pinfunction "2_2") (pintype "passive"))
      (node (ref "R43") (pin "2") (pinfunction "2_2") (pintype "passive"))
      (node (ref "R44") (pin "2") (pinfunction "2_2") (pintype "passive"))
      (node (ref "R45") (pin "2") (pinfunction "2_2") (pintype "passive"))
      (node (ref "R46") (pin "2") (pinfunction "2_2") (pintype "passive"))
      (node (ref "R5") (pin "2") (pinfunction "2_2") (pintype "passive"))
      (node (ref "R6") (pin "1") (pinfunction "1_1") (pintype "passive"))
      (node (ref "R7") (pin "1") (pinfunction "1_1") (pintype "passive"))
      (node (ref "R8") (pin "1") (pinfunction "1_1") (pintype "passive"))
      (node (ref "R9") (pin "1") (pinfunction "1_1") (pintype "passive"))
      (node (ref "SV1") (pin "2") (pinfunction "2_2") (pintype "passive"))
      (node (ref "U$1") (pin "2") (pinfunction "VDD_2") (pintype "power_in"))
    )
    (net (code "2") (name "BTN0") (class "Default")
      (node (ref "IC3") (pin "4") (pinfunction "P0_4") (pintype "bidirectional"))
      (node (ref "S8") (pin "4") (pinfunction "P1_4") (pintype "passive"))
    )
    (net (code "3") (name "BTN1") (class "Default")
      (node (ref "IC3") (pin "5") (pinfunction "P1_5") (pintype "bidirectional"))
      (node (ref "S7") (pin "3") (pinfunction "P_3") (pintype "passive"))
    )
    (net (code "4") (name "BTN2") (class "Default")
      (node (ref "IC3") (pin "6") (pinfunction "P2_6") (pintype "bidirectional"))
      (node (ref "S6") (pin "4") (pinfunction "P1_4") (pintype "passive"))
    )
    (net (code "5") (name "BTN3") (class "Default")
      (node (ref "IC3") (pin "7") (pinfunction "P3_7") (pintype "bidirectional"))
      (node (ref "S5") (pin "3") (pinfunction "P_3") (pintype "passive"))
    )
    (net (code "6") (name "BTN4") (class "Default")
      (node (ref "IC3") (pin "9") (pinfunction "P4_9") (pintype "bidirectional"))
      (node (ref "S4") (pin "3") (pinfunction "P_3") (pintype "passive"))
    )
    (net (code "7") (name "BTN5") (class "Default")
      (node (ref "IC3") (pin "10") (pinfunction "P5_10") (pintype "bidirectional"))
      (node (ref "S3") (pin "4") (pinfunction "P1_4") (pintype "passive"))
    )
    (net (code "8") (name "BTN6") (class "Default")
      (node (ref "IC3") (pin "11") (pinfunction "P6_11") (pintype "bidirectional"))
      (node (ref "S2") (pin "3") (pinfunction "P_3") (pintype "passive"))
    )
    (net (code "9") (name "BTN7") (class "Default")
      (node (ref "IC3") (pin "12") (pinfunction "P7_12") (pintype "bidirectional"))
      (node (ref "S1") (pin "4") (pinfunction "P1_4") (pintype "passive"))
    )
    (net (code "10") (name "D4") (class "Default")
      (node (ref "IC1") (pin "6") (pinfunction "PD4(XCK/T0)_6") (pintype "bidirectional"))
      (node (ref "U$1") (pin "11") (pinfunction "D4_11") (pintype "bidirectional"))
    )
    (net (code "11") (name "D5") (class "Default")
      (node (ref "IC1") (pin "11") (pinfunction "PD5(T1)_11") (pintype "bidirectional"))
      (node (ref "U$1") (pin "12") (pinfunction "D5_12") (pintype "bidirectional"))
    )
    (net (code "12") (name "D6") (class "Default")
      (node (ref "IC1") (pin "12") (pinfunction "PD6(AIN0)_12") (pintype "bidirectional"))
      (node (ref "U$1") (pin "13") (pinfunction "D6_13") (pintype "bidirectional"))
    )
    (net (code "13") (name "D7") (class "Default")
      (node (ref "IC1") (pin "13") (pinfunction "PD7(AIN1)_13") (pintype "bidirectional"))
      (node (ref "U$1") (pin "14") (pinfunction "D7_14") (pintype "bidirectional"))
    )
    (net (code "14") (name "EN") (class "Default")
      (node (ref "IC1") (pin "16") (pinfunction "PB2(SS/OC1B)_16") (pintype "bidirectional"))
      (node (ref "U$1") (pin "6") (pinfunction "E_6") (pintype "input"))
    )
    (net (code "15") (name "GND") (class "Default")
      (node (ref "C1") (pin "2") (pinfunction "2_2") (pintype "passive"))
      (node (ref "C10") (pin "2") (pinfunction "2_2") (pintype "passive"))
      (node (ref "C11") (pin "2") (pinfunction "2_2") (pintype "passive"))
      (node (ref "C12") (pin "2") (pinfunction "2_2") (pintype "passive"))
      (node (ref "C13") (pin "2") (pinfunction "2_2") (pintype "passive"))
      (node (ref "C2") (pin "2") (pinfunction "2_2") (pintype "passive"))
      (node (ref "C3") (pin "2") (pinfunction "2_2") (pintype "passive"))
      (node (ref "C6") (pin "-") (pinfunction "-_-") (pintype "passive"))
      (node (ref "C7") (pin "+") (pinfunction "+_+") (pintype "passive"))
      (node (ref "C8") (pin "2") (pinfunction "2_2") (pintype "passive"))
      (node (ref "IC1") (pin "22") (pinfunction "GND_22") (pintype "power_in"))
      (node (ref "IC1") (pin "8") (pinfunction "GND_8") (pintype "power_in"))
      (node (ref "IC2") (pin "15") (pinfunction "GND_15") (pintype "power_in"))
      (node (ref "IC3") (pin "1") (pinfunction "A0_1") (pintype "input"))
      (node (ref "IC3") (pin "2") (pinfunction "A1_2") (pintype "input"))
      (node (ref "IC3") (pin "3") (pinfunction "A2_3") (pintype "input"))
      (node (ref "IC3") (pin "8") (pinfunction "VSS_8") (pintype "power_in"))
      (node (ref "IC4") (pin "2") (pinfunction "A1_2") (pintype "input"))
      (node (ref "IC4") (pin "3") (pinfunction "A2_3") (pintype "input"))
      (node (ref "IC4") (pin "8") (pinfunction "VSS_8") (pintype "power_in"))
      (node (ref "IC5") (pin "1") (pinfunction "A0_1") (pintype "input"))
      (node (ref "IC5") (pin "3") (pinfunction "A2_3") (pintype "input"))
      (node (ref "IC5") (pin "8") (pinfunction "VSS_8") (pintype "power_in"))
      (node (ref "IC6") (pin "3") (pinfunction "A2_3") (pintype "input"))
      (node (ref "IC6") (pin "8") (pinfunction "VSS_8") (pintype "power_in"))
      (node (ref "R2") (pin "A") (pinfunction "A_A") (pintype "passive"))
      (node (ref "R36") (pin "1") (pinfunction "1_1") (pintype "passive"))
      (node (ref "R37") (pin "1") (pinfunction "1_1") (pintype "passive"))
      (node (ref "R38") (pin "1") (pinfunction "1_1") (pintype "passive"))
      (node (ref "R39") (pin "1") (pinfunction "1_1") (pintype "passive"))
      (node (ref "S1") (pin "1") (pinfunction "S_1") (pintype "passive"))
      (node (ref "S1") (pin "2") (pinfunction "S1_2") (pintype "passive"))
      (node (ref "S2") (pin "1") (pinfunction "S_1") (pintype "passive"))
      (node (ref "S2") (pin "2") (pinfunction "S1_2") (pintype "passive"))
      (node (ref "S3") (pin "1") (pinfunction "S_1") (pintype "passive"))
      (node (ref "S3") (pin "2") (pinfunction "S1_2") (pintype "passive"))
      (node (ref "S4") (pin "1") (pinfunction "S_1") (pintype "passive"))
      (node (ref "S4") (pin "2") (pinfunction "S1_2") (pintype "passive"))
      (node (ref "S5") (pin "1") (pinfunction "S_1") (pintype "passive"))
      (node (ref "S5") (pin "2") (pinfunction "S1_2") (pintype "passive"))
      (node (ref "S6") (pin "1") (pinfunction "S_1") (pintype "passive"))
      (node (ref "S6") (pin "2") (pinfunction "S1_2") (pintype "passive"))
      (node (ref "S7") (pin "1") (pinfunction "S_1") (pintype "passive"))
      (node (ref "S7") (pin "2") (pinfunction "S1_2") (pintype "passive"))
      (node (ref "S8") (pin "1") (pinfunction "S_1") (pintype "passive"))
      (node (ref "S8") (pin "2") (pinfunction "S1_2") (pintype "passive"))
      (node (ref "SV1") (pin "10") (pinfunction "10_10") (pintype "passive"))
      (node (ref "SV1") (pin "4") (pinfunction "4_4") (pintype "passive"))
      (node (ref "SV1") (pin "6") (pinfunction "6_6") (pintype "passive"))
      (node (ref "SV1") (pin "8") (pinfunction "8_8") (pintype "passive"))
      (node (ref "T1") (pin "2") (pinfunction "E_2") (pintype "passive"))
      (node (ref "T10") (pin "2") (pinfunction "E_2") (pintype "passive"))
      (node (ref "T11") (pin "2") (pinfunction "E_2") (pintype "passive"))
      (node (ref "T12") (pin "2") (pinfunction "E_2") (pintype "passive"))
      (node (ref "T13") (pin "2") (pinfunction "E_2") (pintype "passive"))
      (node (ref "T14") (pin "2") (pinfunction "E_2") (pintype "passive"))
      (node (ref "T15") (pin "2") (pinfunction "E_2") (pintype "passive"))
      (node (ref "T16") (pin "2") (pinfunction "E_2") (pintype "passive"))
      (node (ref "T17") (pin "2") (pinfunction "E_2") (pintype "passive"))
      (node (ref "T18") (pin "2") (pinfunction "E_2") (pintype "passive"))
      (node (ref "T19") (pin "2") (pinfunction "E_2") (pintype "passive"))
      (node (ref "T2") (pin "2") (pinfunction "E_2") (pintype "passive"))
      (node (ref "T20") (pin "2") (pinfunction "E_2") (pintype "passive"))
      (node (ref "T21") (pin "2") (pinfunction "E_2") (pintype "passive"))
      (node (ref "T22") (pin "2") (pinfunction "E_2") (pintype "passive"))
      (node (ref "T23") (pin "2") (pinfunction "E_2") (pintype "passive"))
      (node (ref "T24") (pin "2") (pinfunction "E_2") (pintype "passive"))
      (node (ref "T3") (pin "2") (pinfunction "E_2") (pintype "passive"))
      (node (ref "T4") (pin "2") (pinfunction "E_2") (pintype "passive"))
      (node (ref "T5") (pin "2") (pinfunction "E_2") (pintype "passive"))
      (node (ref "T6") (pin "2") (pinfunction "E_2") (pintype "passive"))
      (node (ref "T7") (pin "2") (pinfunction "E_2") (pintype "passive"))
      (node (ref "T8") (pin "2") (pinfunction "E_2") (pintype "passive"))
      (node (ref "T9") (pin "2") (pinfunction "E_2") (pintype "passive"))
      (node (ref "U$1") (pin "1") (pinfunction "VSS_1") (pintype "power_in"))
      (node (ref "U$1") (pin "16") (pinfunction "LED-_16") (pintype "power_in"))
      (node (ref "X1") (pin "1") (pinfunction "1_1") (pintype "passive"))
      (node (ref "X1") (pin "5") (pinfunction "5_5") (pintype "passive"))
    )
    (net (code "16") (name "LED0") (class "Default")
      (node (ref "IC4") (pin "4") (pinfunction "P0_4") (pintype "bidirectional"))
      (node (ref "T1") (pin "1") (pinfunction "B_1") (pintype "passive"))
    )
    (net (code "17") (name "LED1") (class "Default")
      (node (ref "IC4") (pin "5") (pinfunction "P1_5") (pintype "bidirectional"))
      (node (ref "T2") (pin "1") (pinfunction "B_1") (pintype "passive"))
    )
    (net (code "18") (name "LED2") (class "Default")
      (node (ref "IC4") (pin "6") (pinfunction "P2_6") (pintype "bidirectional"))
      (node (ref "T3") (pin "1") (pinfunction "B_1") (pintype "passive"))
    )
    (net (code "19") (name "LED3") (class "Default")
      (node (ref "IC4") (pin "7") (pinfunction "P3_7") (pintype "bidirectional"))
      (node (ref "T4") (pin "1") (pinfunction "B_1") (pintype "passive"))
    )
    (net (code "20") (name "LED4") (class "Default")
      (node (ref "IC4") (pin "9") (pinfunction "P4_9") (pintype "bidirectional"))
      (node (ref "T5") (pin "1") (pinfunction "B_1") (pintype "passive"))
    )
    (net (code "21") (name "LED5") (class "Default")
      (node (ref "IC4") (pin "10") (pinfunction "P5_10") (pintype "bidirectional"))
      (node (ref "T6") (pin "1") (pinfunction "B_1") (pintype "passive"))
    )
    (net (code "22") (name "LED6") (class "Default")
      (node (ref "IC4") (pin "11") (pinfunction "P6_11") (pintype "bidirectional"))
      (node (ref "T7") (pin "1") (pinfunction "B_1") (pintype "passive"))
    )
    (net (code "23") (name "LED7") (class "Default")
      (node (ref "IC4") (pin "12") (pinfunction "P7_12") (pintype "bidirectional"))
      (node (ref "T8") (pin "1") (pinfunction "B_1") (pintype "passive"))
    )
    (net (code "24") (name "LED8") (class "Default")
      (node (ref "IC5") (pin "4") (pinfunction "P0_4") (pintype "bidirectional"))
      (node (ref "T9") (pin "1") (pinfunction "B_1") (pintype "passive"))
    )
    (net (code "25") (name "LED9") (class "Default")
      (node (ref "IC5") (pin "5") (pinfunction "P1_5") (pintype "bidirectional"))
      (node (ref "T10") (pin "1") (pinfunction "B_1") (pintype "passive"))
    )
    (net (code "26") (name "LED10") (class "Default")
      (node (ref "IC5") (pin "6") (pinfunction "P2_6") (pintype "bidirectional"))
      (node (ref "T11") (pin "1") (pinfunction "B_1") (pintype "passive"))
    )
    (net (code "27") (name "LED11") (class "Default")
      (node (ref "IC5") (pin "7") (pinfunction "P3_7") (pintype "bidirectional"))
      (node (ref "T12") (pin "1") (pinfunction "B_1") (pintype "passive"))
    )
    (net (code "28") (name "LED12") (class "Default")
      (node (ref "IC5") (pin "9") (pinfunction "P4_9") (pintype "bidirectional"))
      (node (ref "T13") (pin "1") (pinfunction "B_1") (pintype "passive"))
    )
    (net (code "29") (name "LED13") (class "Default")
      (node (ref "IC5") (pin "10") (pinfunction "P5_10") (pintype "bidirectional"))
      (node (ref "T14") (pin "1") (pinfunction "B_1") (pintype "passive"))
    )
    (net (code "30") (name "LED14") (class "Default")
      (node (ref "IC5") (pin "11") (pinfunction "P6_11") (pintype "bidirectional"))
      (node (ref "T15") (pin "1") (pinfunction "B_1") (pintype "passive"))
    )
    (net (code "31") (name "LED15") (class "Default")
      (node (ref "IC5") (pin "12") (pinfunction "P7_12") (pintype "bidirectional"))
      (node (ref "T16") (pin "1") (pinfunction "B_1") (pintype "passive"))
    )
    (net (code "32") (name "LED16") (class "Default")
      (node (ref "IC6") (pin "4") (pinfunction "P0_4") (pintype "bidirectional"))
      (node (ref "T17") (pin "1") (pinfunction "B_1") (pintype "passive"))
    )
    (net (code "33") (name "LED17") (class "Default")
      (node (ref "IC6") (pin "5") (pinfunction "P1_5") (pintype "bidirectional"))
      (node (ref "T18") (pin "1") (pinfunction "B_1") (pintype "passive"))
    )
    (net (code "34") (name "LED18") (class "Default")
      (node (ref "IC6") (pin "6") (pinfunction "P2_6") (pintype "bidirectional"))
      (node (ref "T19") (pin "1") (pinfunction "B_1") (pintype "passive"))
    )
    (net (code "35") (name "LED19") (class "Default")
      (node (ref "IC6") (pin "7") (pinfunction "P3_7") (pintype "bidirectional"))
      (node (ref "T20") (pin "1") (pinfunction "B_1") (pintype "passive"))
    )
    (net (code "36") (name "LED20") (class "Default")
      (node (ref "IC6") (pin "9") (pinfunction "P4_9") (pintype "bidirectional"))
      (node (ref "T21") (pin "1") (pinfunction "B_1") (pintype "passive"))
    )
    (net (code "37") (name "LED21") (class "Default")
      (node (ref "IC6") (pin "10") (pinfunction "P5_10") (pintype "bidirectional"))
      (node (ref "T22") (pin "1") (pinfunction "B_1") (pintype "passive"))
    )
    (net (code "38") (name "LED22") (class "Default")
      (node (ref "IC6") (pin "11") (pinfunction "P6_11") (pintype "bidirectional"))
      (node (ref "T23") (pin "1") (pinfunction "B_1") (pintype "passive"))
    )
    (net (code "39") (name "LED23") (class "Default")
      (node (ref "IC6") (pin "12") (pinfunction "P7_12") (pintype "bidirectional"))
      (node (ref "T24") (pin "1") (pinfunction "B_1") (pintype "passive"))
    )
    (net (code "40") (name "MISO") (class "Default")
      (node (ref "IC1") (pin "18") (pinfunction "PB4(MISO)_18") (pintype "bidirectional"))
      (node (ref "SV1") (pin "9") (pinfunction "9_9") (pintype "passive"))
    )
    (net (code "41") (name "MOSI") (class "Default")
      (node (ref "IC1") (pin "17") (pinfunction "PB3(MOSI/OC2)_17") (pintype "bidirectional"))
      (node (ref "SV1") (pin "1") (pinfunction "1_1") (pintype "passive"))
    )
    (net (code "42") (name "Net-(IC1-PB6(XTAL1{slash}TOSC1))") (class "Default")
      (node (ref "C2") (pin "1") (pinfunction "1_1") (pintype "passive"))
      (node (ref "IC1") (pin "9") (pinfunction "PB6(XTAL1/TOSC1)_9") (pintype "bidirectional"))
      (node (ref "Q1") (pin "1") (pinfunction "1_1") (pintype "passive"))
    )
    (net (code "43") (name "Net-(IC1-PB7(XTAL2{slash}TOSC2))") (class "Default")
      (node (ref "C3") (pin "1") (pinfunction "1_1") (pintype "passive"))
      (node (ref "IC1") (pin "10") (pinfunction "PB7(XTAL2/TOSC2)_10") (pintype "bidirectional"))
      (node (ref "Q1") (pin "2") (pinfunction "2_2") (pintype "passive"))
    )
    (net (code "44") (name "Net-(IC1-PC0(ADC0))") (class "Default")
      (node (ref "IC1") (pin "23") (pinfunction "PC0(ADC0)_23") (pintype "bidirectional"))
      (node (ref "LED28") (pin "A") (pinfunction "A_A") (pintype "passive"))
    )
    (net (code "45") (name "Net-(IC1-PC1(ADC1))") (class "Default")
      (node (ref "IC1") (pin "24") (pinfunction "PC1(ADC1)_24") (pintype "bidirectional"))
      (node (ref "LED27") (pin "A") (pinfunction "A_A") (pintype "passive"))
    )
    (net (code "46") (name "Net-(IC1-PC2(ADC2))") (class "Default")
      (node (ref "IC1") (pin "25") (pinfunction "PC2(ADC2)_25") (pintype "bidirectional"))
      (node (ref "LED26") (pin "A") (pinfunction "A_A") (pintype "passive"))
    )
    (net (code "47") (name "Net-(IC1-PC3(ADC3))") (class "Default")
      (node (ref "IC1") (pin "26") (pinfunction "PC3(ADC3)_26") (pintype "bidirectional"))
      (node (ref "LED25") (pin "A") (pinfunction "A_A") (pintype "passive"))
    )
    (net (code "48") (name "Net-(IC2A-C1+)") (class "Default")
      (node (ref "C4") (pin "+") (pinfunction "+_+") (pintype "passive"))
      (node (ref "IC2") (pin "1") (pinfunction "C1+_1") (pintype "bidirectional"))
    )
    (net (code "49") (name "Net-(IC2A-C1-)") (class "Default")
      (node (ref "C4") (pin "-") (pinfunction "-_-") (pintype "passive"))
      (node (ref "IC2") (pin "3") (pinfunction "C1-_3") (pintype "bidirectional"))
    )
    (net (code "50") (name "Net-(IC2A-C2+)") (class "Default")
      (node (ref "C5") (pin "+") (pinfunction "+_+") (pintype "passive"))
      (node (ref "IC2") (pin "4") (pinfunction "C2+_4") (pintype "bidirectional"))
    )
    (net (code "51") (name "Net-(IC2A-C2-)") (class "Default")
      (node (ref "C5") (pin "-") (pinfunction "-_-") (pintype "passive"))
      (node (ref "IC2") (pin "5") (pinfunction "C2-_5") (pintype "bidirectional"))
    )
    (net (code "52") (name "Net-(IC2A-V+)") (class "Default")
      (node (ref "C6") (pin "+") (pinfunction "+_+") (pintype "passive"))
      (node (ref "IC2") (pin "2") (pinfunction "V+_2") (pintype "bidirectional"))
    )
    (net (code "53") (name "Net-(IC2A-V-)") (class "Default")
      (node (ref "C7") (pin "-") (pinfunction "-_-") (pintype "passive"))
      (node (ref "IC2") (pin "6") (pinfunction "V-_6") (pintype "bidirectional"))
    )
    (net (code "54") (name "Net-(IC3-~{INT})") (class "Default")
      (node (ref "IC3") (pin "13") (pinfunction "~{INT}_13") (pintype "output"))
      (node (ref "R6") (pin "2") (pinfunction "2_2") (pintype "passive"))
    )
    (net (code "55") (name "Net-(IC4-~{INT})") (class "Default")
      (node (ref "IC4") (pin "13") (pinfunction "~{INT}_13") (pintype "output"))
      (node (ref "R7") (pin "2") (pinfunction "2_2") (pintype "passive"))
    )
    (net (code "56") (name "Net-(IC5-~{INT})") (class "Default")
      (node (ref "IC5") (pin "13") (pinfunction "~{INT}_13") (pintype "output"))
      (node (ref "R8") (pin "2") (pinfunction "2_2") (pintype "passive"))
    )
    (net (code "57") (name "Net-(IC6-~{INT})") (class "Default")
      (node (ref "IC6") (pin "13") (pinfunction "~{INT}_13") (pintype "output"))
      (node (ref "R9") (pin "2") (pinfunction "2_2") (pintype "passive"))
    )
    (net (code "58") (name "Net-(JP1-Pad1)") (class "Default")
      (node (ref "JP1") (pin "1") (pinfunction "1_1") (pintype "passive"))
      (node (ref "X1") (pin "9") (pinfunction "9_9") (pintype "passive"))
    )
    (net (code "59") (name "Net-(LED1-C)") (class "Default")
      (node (ref "LED1") (pin "K") (pinfunction "C_K") (pintype "passive"))
      (node (ref "T1") (pin "3") (pinfunction "C_3") (pintype "passive"))
    )
    (net (code "60") (name "Net-(LED1-PadA)") (class "Default")
      (node (ref "LED1") (pin "A") (pinfunction "A_A") (pintype "passive"))
      (node (ref "R12") (pin "1") (pinfunction "1_1") (pintype "passive"))
    )
    (net (code "61") (name "Net-(LED2-C)") (class "Default")
      (node (ref "LED2") (pin "K") (pinfunction "C_K") (pintype "passive"))
      (node (ref "T2") (pin "3") (pinfunction "C_3") (pintype "passive"))
    )
    (net (code "62") (name "Net-(LED2-PadA)") (class "Default")
      (node (ref "LED2") (pin "A") (pinfunction "A_A") (pintype "passive"))
      (node (ref "R13") (pin "1") (pinfunction "1_1") (pintype "passive"))
    )
    (net (code "63") (name "Net-(LED3-C)") (class "Default")
      (node (ref "LED3") (pin "K") (pinfunction "C_K") (pintype "passive"))
      (node (ref "T3") (pin "3") (pinfunction "C_3") (pintype "passive"))
    )
    (net (code "64") (name "Net-(LED3-PadA)") (class "Default")
      (node (ref "LED3") (pin "A") (pinfunction "A_A") (pintype "passive"))
      (node (ref "R14") (pin "1") (pinfunction "1_1") (pintype "passive"))
    )
    (net (code "65") (name "Net-(LED4-C)") (class "Default")
      (node (ref "LED4") (pin "K") (pinfunction "C_K") (pintype "passive"))
      (node (ref "T4") (pin "3") (pinfunction "C_3") (pintype "passive"))
    )
    (net (code "66") (name "Net-(LED4-PadA)") (class "Default")
      (node (ref "LED4") (pin "A") (pinfunction "A_A") (pintype "passive"))
      (node (ref "R15") (pin "1") (pinfunction "1_1") (pintype "passive"))
    )
    (net (code "67") (name "Net-(LED5-C)") (class "Default")
      (node (ref "LED5") (pin "K") (pinfunction "C_K") (pintype "passive"))
      (node (ref "T5") (pin "3") (pinfunction "C_3") (pintype "passive"))
    )
    (net (code "68") (name "Net-(LED5-PadA)") (class "Default")
      (node (ref "LED5") (pin "A") (pinfunction "A_A") (pintype "passive"))
      (node (ref "R16") (pin "1") (pinfunction "1_1") (pintype "passive"))
    )
    (net (code "69") (name "Net-(LED6-C)") (class "Default")
      (node (ref "LED6") (pin "K") (pinfunction "C_K") (pintype "passive"))
      (node (ref "T6") (pin "3") (pinfunction "C_3") (pintype "passive"))
    )
    (net (code "70") (name "Net-(LED6-PadA)") (class "Default")
      (node (ref "LED6") (pin "A") (pinfunction "A_A") (pintype "passive"))
      (node (ref "R17") (pin "1") (pinfunction "1_1") (pintype "passive"))
    )
    (net (code "71") (name "Net-(LED7-C)") (class "Default")
      (node (ref "LED7") (pin "K") (pinfunction "C_K") (pintype "passive"))
      (node (ref "T7") (pin "3") (pinfunction "C_3") (pintype "passive"))
    )
    (net (code "72") (name "Net-(LED7-PadA)") (class "Default")
      (node (ref "LED7") (pin "A") (pinfunction "A_A") (pintype "passive"))
      (node (ref "R18") (pin "1") (pinfunction "1_1") (pintype "passive"))
    )
    (net (code "73") (name "Net-(LED8-C)") (class "Default")
      (node (ref "LED8") (pin "K") (pinfunction "C_K") (pintype "passive"))
      (node (ref "T8") (pin "3") (pinfunction "C_3") (pintype "passive"))
    )
    (net (code "74") (name "Net-(LED8-PadA)") (class "Default")
      (node (ref "LED8") (pin "A") (pinfunction "A_A") (pintype "passive"))
      (node (ref "R19") (pin "1") (pinfunction "1_1") (pintype "passive"))
    )
    (net (code "75") (name "Net-(LED9-C)") (class "Default")
      (node (ref "LED9") (pin "K") (pinfunction "C_K") (pintype "passive"))
      (node (ref "T9") (pin "3") (pinfunction "C_3") (pintype "passive"))
    )
    (net (code "76") (name "Net-(LED9-PadA)") (class "Default")
      (node (ref "LED9") (pin "A") (pinfunction "A_A") (pintype "passive"))
      (node (ref "R20") (pin "1") (pinfunction "1_1") (pintype "passive"))
    )
    (net (code "77") (name "Net-(LED10-C)") (class "Default")
      (node (ref "LED10") (pin "K") (pinfunction "C_K") (pintype "passive"))
      (node (ref "T10") (pin "3") (pinfunction "C_3") (pintype "passive"))
    )
    (net (code "78") (name "Net-(LED10-PadA)") (class "Default")
      (node (ref "LED10") (pin "A") (pinfunction "A_A") (pintype "passive"))
      (node (ref "R21") (pin "1") (pinfunction "1_1") (pintype "passive"))
    )
    (net (code "79") (name "Net-(LED11-C)") (class "Default")
      (node (ref "LED11") (pin "K") (pinfunction "C_K") (pintype "passive"))
      (node (ref "T11") (pin "3") (pinfunction "C_3") (pintype "passive"))
    )
    (net (code "80") (name "Net-(LED11-PadA)") (class "Default")
      (node (ref "LED11") (pin "A") (pinfunction "A_A") (pintype "passive"))
      (node (ref "R22") (pin "1") (pinfunction "1_1") (pintype "passive"))
    )
    (net (code "81") (name "Net-(LED12-C)") (class "Default")
      (node (ref "LED12") (pin "K") (pinfunction "C_K") (pintype "passive"))
      (node (ref "T12") (pin "3") (pinfunction "C_3") (pintype "passive"))
    )
    (net (code "82") (name "Net-(LED12-PadA)") (class "Default")
      (node (ref "LED12") (pin "A") (pinfunction "A_A") (pintype "passive"))
      (node (ref "R23") (pin "1") (pinfunction "1_1") (pintype "passive"))
    )
    (net (code "83") (name "Net-(LED13-C)") (class "Default")
      (node (ref "LED13") (pin "K") (pinfunction "C_K") (pintype "passive"))
      (node (ref "T13") (pin "3") (pinfunction "C_3") (pintype "passive"))
    )
    (net (code "84") (name "Net-(LED13-PadA)") (class "Default")
      (node (ref "LED13") (pin "A") (pinfunction "A_A") (pintype "passive"))
      (node (ref "R24") (pin "1") (pinfunction "1_1") (pintype "passive"))
    )
    (net (code "85") (name "Net-(LED14-C)") (class "Default")
      (node (ref "LED14") (pin "K") (pinfunction "C_K") (pintype "passive"))
      (node (ref "T14") (pin "3") (pinfunction "C_3") (pintype "passive"))
    )
    (net (code "86") (name "Net-(LED14-PadA)") (class "Default")
      (node (ref "LED14") (pin "A") (pinfunction "A_A") (pintype "passive"))
      (node (ref "R25") (pin "1") (pinfunction "1_1") (pintype "passive"))
    )
    (net (code "87") (name "Net-(LED15-C)") (class "Default")
      (node (ref "LED15") (pin "K") (pinfunction "C_K") (pintype "passive"))
      (node (ref "T15") (pin "3") (pinfunction "C_3") (pintype "passive"))
    )
    (net (code "88") (name "Net-(LED15-PadA)") (class "Default")
      (node (ref "LED15") (pin "A") (pinfunction "A_A") (pintype "passive"))
      (node (ref "R26") (pin "1") (pinfunction "1_1") (pintype "passive"))
    )
    (net (code "89") (name "Net-(LED16-C)") (class "Default")
      (node (ref "LED16") (pin "K") (pinfunction "C_K") (pintype "passive"))
      (node (ref "T16") (pin "3") (pinfunction "C_3") (pintype "passive"))
    )
    (net (code "90") (name "Net-(LED16-PadA)") (class "Default")
      (node (ref "LED16") (pin "A") (pinfunction "A_A") (pintype "passive"))
      (node (ref "R27") (pin "1") (pinfunction "1_1") (pintype "passive"))
    )
    (net (code "91") (name "Net-(LED17-C)") (class "Default")
      (node (ref "LED17") (pin "K") (pinfunction "C_K") (pintype "passive"))
      (node (ref "T17") (pin "3") (pinfunction "C_3") (pintype "passive"))
    )
    (net (code "92") (name "Net-(LED17-PadA)") (class "Default")
      (node (ref "LED17") (pin "A") (pinfunction "A_A") (pintype "passive"))
      (node (ref "R28") (pin "1") (pinfunction "1_1") (pintype "passive"))
    )
    (net (code "93") (name "Net-(LED18-C)") (class "Default")
      (node (ref "LED18") (pin "K") (pinfunction "C_K") (pintype "passive"))
      (node (ref "T18") (pin "3") (pinfunction "C_3") (pintype "passive"))
    )
    (net (code "94") (name "Net-(LED18-PadA)") (class "Default")
      (node (ref "LED18") (pin "A") (pinfunction "A_A") (pintype "passive"))
      (node (ref "R29") (pin "1") (pinfunction "1_1") (pintype "passive"))
    )
    (net (code "95") (name "Net-(LED19-C)") (class "Default")
      (node (ref "LED19") (pin "K") (pinfunction "C_K") (pintype "passive"))
      (node (ref "T19") (pin "3") (pinfunction "C_3") (pintype "passive"))
    )
    (net (code "96") (name "Net-(LED19-PadA)") (class "Default")
      (node (ref "LED19") (pin "A") (pinfunction "A_A") (pintype "passive"))
      (node (ref "R30") (pin "1") (pinfunction "1_1") (pintype "passive"))
    )
    (net (code "97") (name "Net-(LED20-C)") (class "Default")
      (node (ref "LED20") (pin "K") (pinfunction "C_K") (pintype "passive"))
      (node (ref "T20") (pin "3") (pinfunction "C_3") (pintype "passive"))
    )
    (net (code "98") (name "Net-(LED20-PadA)") (class "Default")
      (node (ref "LED20") (pin "A") (pinfunction "A_A") (pintype "passive"))
      (node (ref "R31") (pin "1") (pinfunction "1_1") (pintype "passive"))
    )
    (net (code "99") (name "Net-(LED21-C)") (class "Default")
      (node (ref "LED21") (pin "K") (pinfunction "C_K") (pintype "passive"))
      (node (ref "T21") (pin "3") (pinfunction "C_3") (pintype "passive"))
    )
    (net (code "100") (name "Net-(LED21-PadA)") (class "Default")
      (node (ref "LED21") (pin "A") (pinfunction "A_A") (pintype "passive"))
      (node (ref "R32") (pin "1") (pinfunction "1_1") (pintype "passive"))
    )
    (net (code "101") (name "Net-(LED22-C)") (class "Default")
      (node (ref "LED22") (pin "K") (pinfunction "C_K") (pintype "passive"))
      (node (ref "T22") (pin "3") (pinfunction "C_3") (pintype "passive"))
    )
    (net (code "102") (name "Net-(LED22-PadA)") (class "Default")
      (node (ref "LED22") (pin "A") (pinfunction "A_A") (pintype "passive"))
      (node (ref "R33") (pin "1") (pinfunction "1_1") (pintype "passive"))
    )
    (net (code "103") (name "Net-(LED23-C)") (class "Default")
      (node (ref "LED23") (pin "K") (pinfunction "C_K") (pintype "passive"))
      (node (ref "T23") (pin "3") (pinfunction "C_3") (pintype "passive"))
    )
    (net (code "104") (name "Net-(LED23-PadA)") (class "Default")
      (node (ref "LED23") (pin "A") (pinfunction "A_A") (pintype "passive"))
      (node (ref "R34") (pin "1") (pinfunction "1_1") (pintype "passive"))
    )
    (net (code "105") (name "Net-(LED24-C)") (class "Default")
      (node (ref "LED24") (pin "K") (pinfunction "C_K") (pintype "passive"))
      (node (ref "T24") (pin "3") (pinfunction "C_3") (pintype "passive"))
    )
    (net (code "106") (name "Net-(LED24-PadA)") (class "Default")
      (node (ref "LED24") (pin "A") (pinfunction "A_A") (pintype "passive"))
      (node (ref "R35") (pin "1") (pinfunction "1_1") (pintype "passive"))
    )
    (net (code "107") (name "Net-(LED25-C)") (class "Default")
      (node (ref "LED25") (pin "K") (pinfunction "C_K") (pintype "passive"))
      (node (ref "R36") (pin "2") (pinfunction "2_2") (pintype "passive"))
    )
    (net (code "108") (name "Net-(LED26-C)") (class "Default")
      (node (ref "LED26") (pin "K") (pinfunction "C_K") (pintype "passive"))
      (node (ref "R37") (pin "2") (pinfunction "2_2") (pintype "passive"))
    )
    (net (code "109") (name "Net-(LED27-C)") (class "Default")
      (node (ref "LED27") (pin "K") (pinfunction "C_K") (pintype "passive"))
      (node (ref "R38") (pin "2") (pinfunction "2_2") (pintype "passive"))
    )
    (net (code "110") (name "Net-(LED28-C)") (class "Default")
      (node (ref "LED28") (pin "K") (pinfunction "C_K") (pintype "passive"))
      (node (ref "R39") (pin "2") (pinfunction "2_2") (pintype "passive"))
    )
    (net (code "111") (name "Net-(R2-PadE)") (class "Default")
      (node (ref "R2") (pin "E") (pinfunction "E_E") (pintype "passive"))
      (node (ref "R3") (pin "2") (pinfunction "2_2") (pintype "passive"))
    )
    (net (code "112") (name "Net-(S1-P)") (class "Default")
      (node (ref "R46") (pin "1") (pinfunction "1_1") (pintype "passive"))
      (node (ref "S1") (pin "3") (pinfunction "P_3") (pintype "passive"))
    )
    (net (code "113") (name "Net-(S2-P1)") (class "Default")
      (node (ref "R45") (pin "1") (pinfunction "1_1") (pintype "passive"))
      (node (ref "S2") (pin "4") (pinfunction "P1_4") (pintype "passive"))
    )
    (net (code "114") (name "Net-(S3-P)") (class "Default")
      (node (ref "R44") (pin "1") (pinfunction "1_1") (pintype "passive"))
      (node (ref "S3") (pin "3") (pinfunction "P_3") (pintype "passive"))
    )
    (net (code "115") (name "Net-(S4-P1)") (class "Default")
      (node (ref "R43") (pin "1") (pinfunction "1_1") (pintype "passive"))
      (node (ref "S4") (pin "4") (pinfunction "P1_4") (pintype "passive"))
    )
    (net (code "116") (name "Net-(S5-P1)") (class "Default")
      (node (ref "R42") (pin "1") (pinfunction "1_1") (pintype "passive"))
      (node (ref "S5") (pin "4") (pinfunction "P1_4") (pintype "passive"))
    )
    (net (code "117") (name "Net-(S6-P)") (class "Default")
      (node (ref "R41") (pin "1") (pinfunction "1_1") (pintype "passive"))
      (node (ref "S6") (pin "3") (pinfunction "P_3") (pintype "passive"))
    )
    (net (code "118") (name "Net-(S7-P1)") (class "Default")
      (node (ref "R40") (pin "1") (pinfunction "1_1") (pintype "passive"))
      (node (ref "S7") (pin "4") (pinfunction "P1_4") (pintype "passive"))
    )
    (net (code "119") (name "Net-(S8-P)") (class "Default")
      (node (ref "R4") (pin "1") (pinfunction "1_1") (pintype "passive"))
      (node (ref "S8") (pin "3") (pinfunction "P_3") (pintype "passive"))
    )
    (net (code "120") (name "Net-(U$1-LED+)") (class "Default")
      (node (ref "R5") (pin "1") (pinfunction "1_1") (pintype "passive"))
      (node (ref "U$1") (pin "15") (pinfunction "LED+_15") (pintype "power_in"))
    )
    (net (code "121") (name "Net-(U$1-VEE)") (class "Default")
      (node (ref "R2") (pin "S") (pinfunction "S_S") (pintype "passive"))
      (node (ref "U$1") (pin "3") (pinfunction "VEE_3") (pintype "input"))
    )
    (net (code "122") (name "RESET") (class "Default")
      (node (ref "C1") (pin "1") (pinfunction "1_1") (pintype "passive"))
      (node (ref "IC1") (pin "1") (pinfunction "PC6(/RESET)_1") (pintype "bidirectional"))
      (node (ref "R1") (pin "1") (pinfunction "1_1") (pintype "passive"))
      (node (ref "SV1") (pin "5") (pinfunction "5_5") (pintype "passive"))
    )
    (net (code "123") (name "RS") (class "Default")
      (node (ref "IC1") (pin "14") (pinfunction "PB0(ICP)_14") (pintype "bidirectional"))
      (node (ref "U$1") (pin "4") (pinfunction "RS_4") (pintype "input"))
    )
    (net (code "124") (name "RS232RX") (class "Default")
      (node (ref "IC2") (pin "14") (pinfunction "T1OUT_14") (pintype "output"))
      (node (ref "JP2") (pin "1") (pinfunction "1_1") (pintype "passive"))
      (node (ref "JP2") (pin "6") (pinfunction "6_6") (pintype "passive"))
    )
    (net (code "125") (name "RS232RX_CON") (class "Default")
      (node (ref "JP2") (pin "3") (pinfunction "3_3") (pintype "passive"))
      (node (ref "X1") (pin "2") (pinfunction "2_2") (pintype "passive"))
    )
    (net (code "126") (name "RS232TX") (class "Default")
      (node (ref "IC2") (pin "13") (pinfunction "R1IN_13") (pintype "input"))
      (node (ref "JP2") (pin "2") (pinfunction "2_2") (pintype "passive"))
      (node (ref "JP2") (pin "5") (pinfunction "5_5") (pintype "passive"))
    )
    (net (code "127") (name "RS232TX_CON") (class "Default")
      (node (ref "JP2") (pin "4") (pinfunction "4_4") (pintype "passive"))
      (node (ref "X1") (pin "3") (pinfunction "3_3") (pintype "passive"))
    )
    (net (code "128") (name "RW") (class "Default")
      (node (ref "IC1") (pin "15") (pinfunction "PB1(OC1A)_15") (pintype "bidirectional"))
      (node (ref "U$1") (pin "5") (pinfunction "R/W_5") (pintype "input"))
    )
    (net (code "129") (name "RXD") (class "Default")
      (node (ref "IC1") (pin "2") (pinfunction "PD0(RXD)_2") (pintype "bidirectional"))
      (node (ref "IC2") (pin "12") (pinfunction "R1OUT_12") (pintype "output"))
    )
    (net (code "130") (name "SCK") (class "Default")
      (node (ref "IC1") (pin "19") (pinfunction "PB5(SCK)_19") (pintype "bidirectional"))
      (node (ref "SV1") (pin "7") (pinfunction "7_7") (pintype "passive"))
    )
    (net (code "131") (name "SCL") (class "Default")
      (node (ref "IC1") (pin "28") (pinfunction "PC5(ADC5/SCL)_28") (pintype "bidirectional"))
      (node (ref "IC3") (pin "14") (pinfunction "SCL_14") (pintype "input"))
      (node (ref "IC4") (pin "14") (pinfunction "SCL_14") (pintype "input"))
      (node (ref "IC5") (pin "14") (pinfunction "SCL_14") (pintype "input"))
      (node (ref "IC6") (pin "14") (pinfunction "SCL_14") (pintype "input"))
      (node (ref "R11") (pin "1") (pinfunction "1_1") (pintype "passive"))
    )
    (net (code "132") (name "SDA") (class "Default")
      (node (ref "IC1") (pin "27") (pinfunction "PC4(ADC4/SDA)_27") (pintype "bidirectional"))
      (node (ref "IC3") (pin "15") (pinfunction "SDA_15") (pintype "bidirectional"))
      (node (ref "IC4") (pin "15") (pinfunction "SDA_15") (pintype "bidirectional"))
      (node (ref "IC5") (pin "15") (pinfunction "SDA_15") (pintype "bidirectional"))
      (node (ref "IC6") (pin "15") (pinfunction "SDA_15") (pintype "bidirectional"))
      (node (ref "R10") (pin "1") (pinfunction "1_1") (pintype "passive"))
    )
    (net (code "133") (name "TXD") (class "Default")
      (node (ref "IC1") (pin "3") (pinfunction "PD1(TXD)_3") (pintype "bidirectional"))
      (node (ref "IC2") (pin "11") (pinfunction "T1IN_11") (pintype "input"))
    )
    (net (code "134") (name "unconnected-(IC1-PD2(INT0)-Pad4)") (class "Default")
      (node (ref "IC1") (pin "4") (pinfunction "PD2(INT0)_4") (pintype "bidirectional"))
    )
    (net (code "135") (name "unconnected-(IC1-PD3(INT1)-Pad5)") (class "Default")
      (node (ref "IC1") (pin "5") (pinfunction "PD3(INT1)_5") (pintype "bidirectional"))
    )
    (net (code "136") (name "unconnected-(IC2A-R2IN-Pad8)") (class "Default")
      (node (ref "IC2") (pin "8") (pinfunction "R2IN_8") (pintype "input"))
    )
    (net (code "137") (name "unconnected-(IC2A-R2OUT-Pad9)") (class "Default")
      (node (ref "IC2") (pin "9") (pinfunction "R2OUT_9") (pintype "output"))
    )
    (net (code "138") (name "unconnected-(IC2A-T2IN-Pad10)") (class "Default")
      (node (ref "IC2") (pin "10") (pinfunction "T2IN_10") (pintype "input"))
    )
    (net (code "139") (name "unconnected-(IC2A-T2OUT-Pad7)") (class "Default")
      (node (ref "IC2") (pin "7") (pinfunction "T2OUT_7") (pintype "output"))
    )
    (net (code "140") (name "unconnected-(SV1-Pad3)") (class "Default")
      (node (ref "SV1") (pin "3") (pinfunction "3_3") (pintype "passive"))
    )
    (net (code "141") (name "unconnected-(U$1-D0-Pad7)") (class "Default")
      (node (ref "U$1") (pin "7") (pinfunction "D0_7") (pintype "bidirectional"))
    )
    (net (code "142") (name "unconnected-(U$1-D1-Pad8)") (class "Default")
      (node (ref "U$1") (pin "8") (pinfunction "D1_8") (pintype "bidirectional"))
    )
    (net (code "143") (name "unconnected-(U$1-D2-Pad9)") (class "Default")
      (node (ref "U$1") (pin "9") (pinfunction "D2_9") (pintype "bidirectional"))
    )
    (net (code "144") (name "unconnected-(U$1-D3-Pad10)") (class "Default")
      (node (ref "U$1") (pin "10") (pinfunction "D3_10") (pintype "bidirectional"))
    )
    (net (code "145") (name "unconnected-(X1-Pad4)") (class "Default")
      (node (ref "X1") (pin "4") (pinfunction "4_4") (pintype "passive"))
    )
    (net (code "146") (name "unconnected-(X1-Pad6)") (class "Default")
      (node (ref "X1") (pin "6") (pinfunction "6_6") (pintype "passive"))
    )
    (net (code "147") (name "unconnected-(X1-Pad7)") (class "Default")
      (node (ref "X1") (pin "7") (pinfunction "7_7") (pintype "passive"))
    )
    (net (code "148") (name "unconnected-(X1-Pad8)") (class "Default")
      (node (ref "X1") (pin "8") (pinfunction "8_8") (pintype "passive"))
    )
  )
)
